# DATALOGGER_CA_ADC_V1.net
KiCad netlist of a schematic drawn in EAGLE
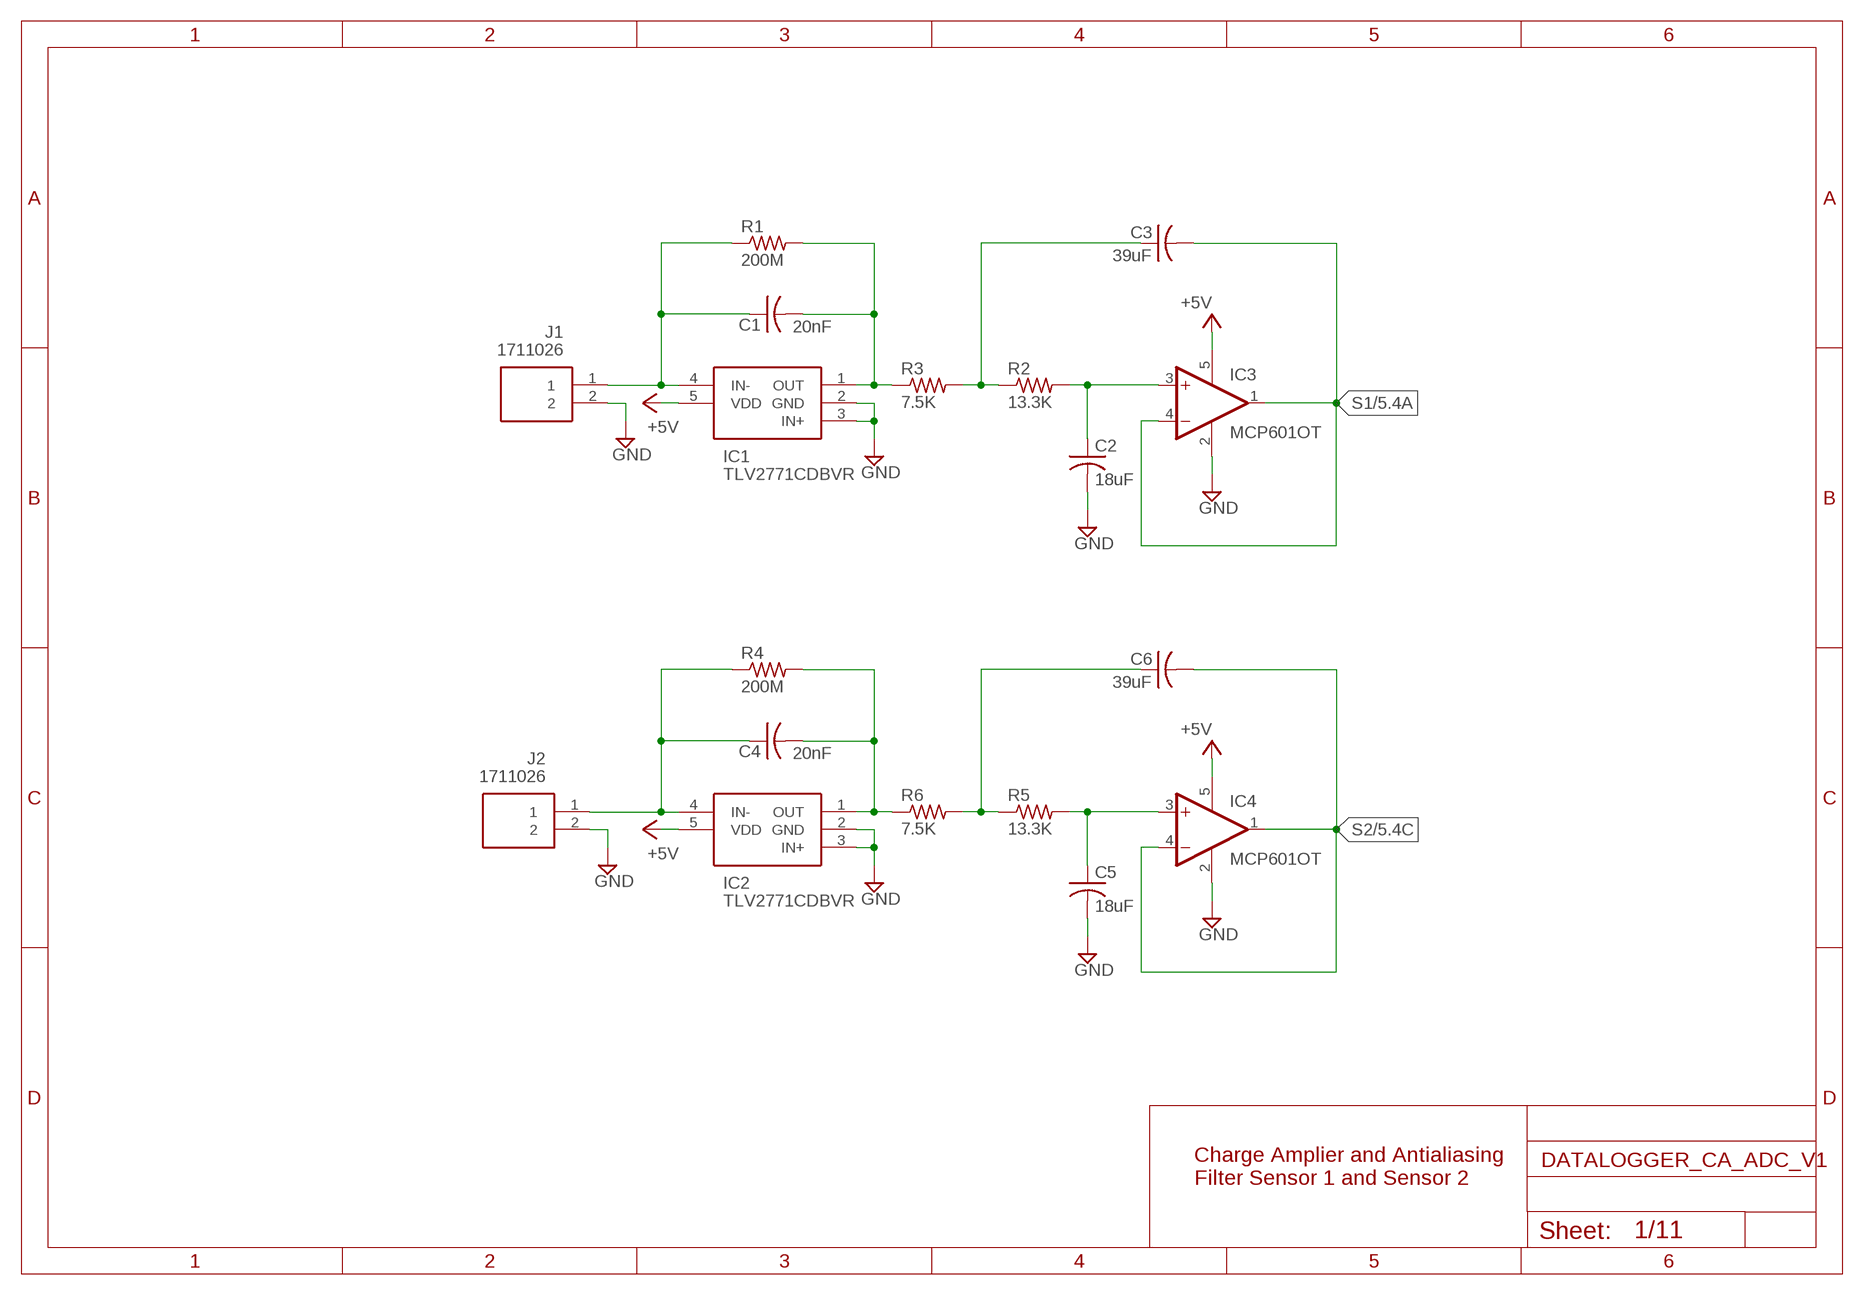
[diagram p0: schematic, sheet 1]
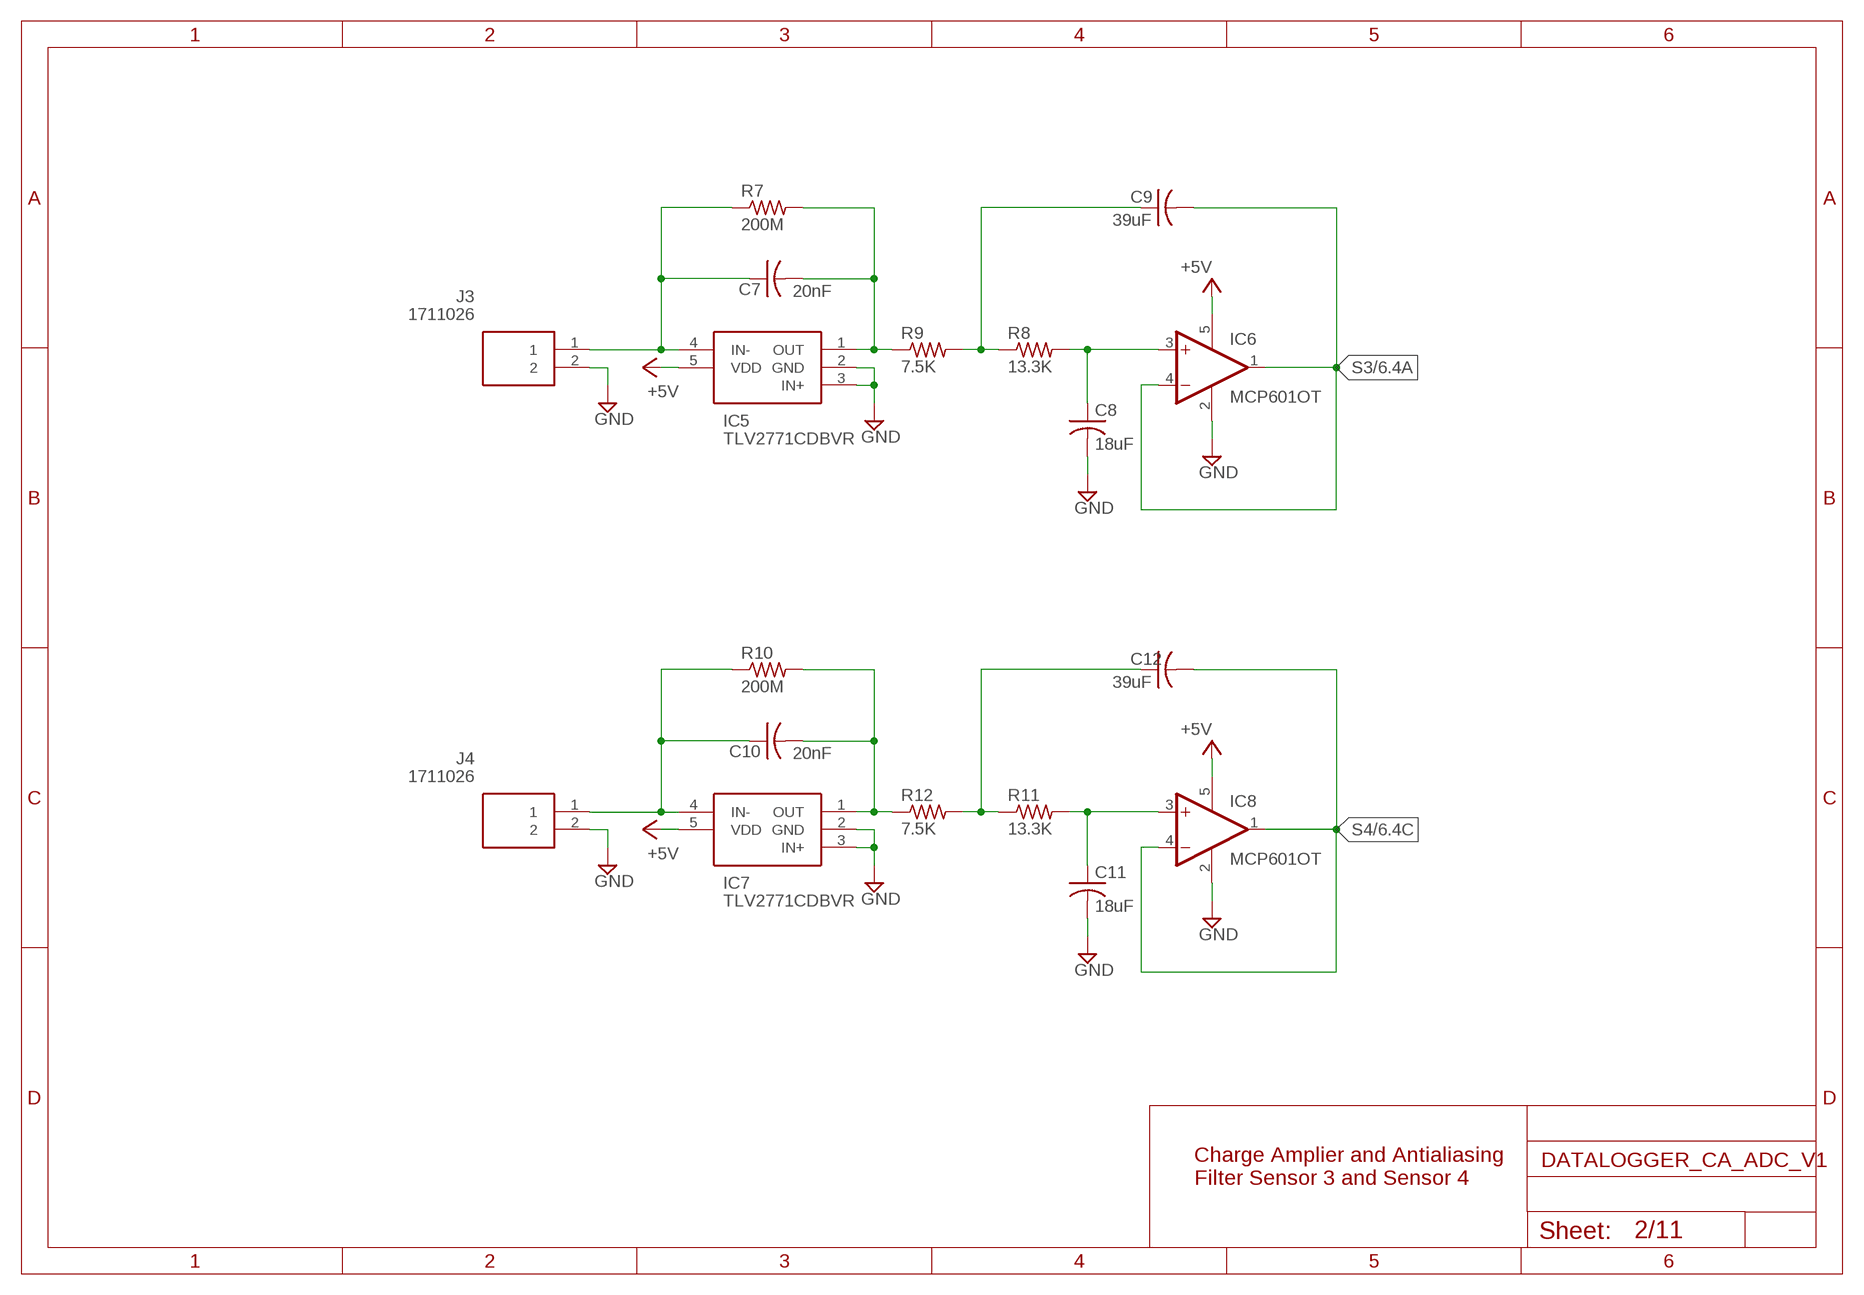
[diagram p1: schematic, sheet 2]
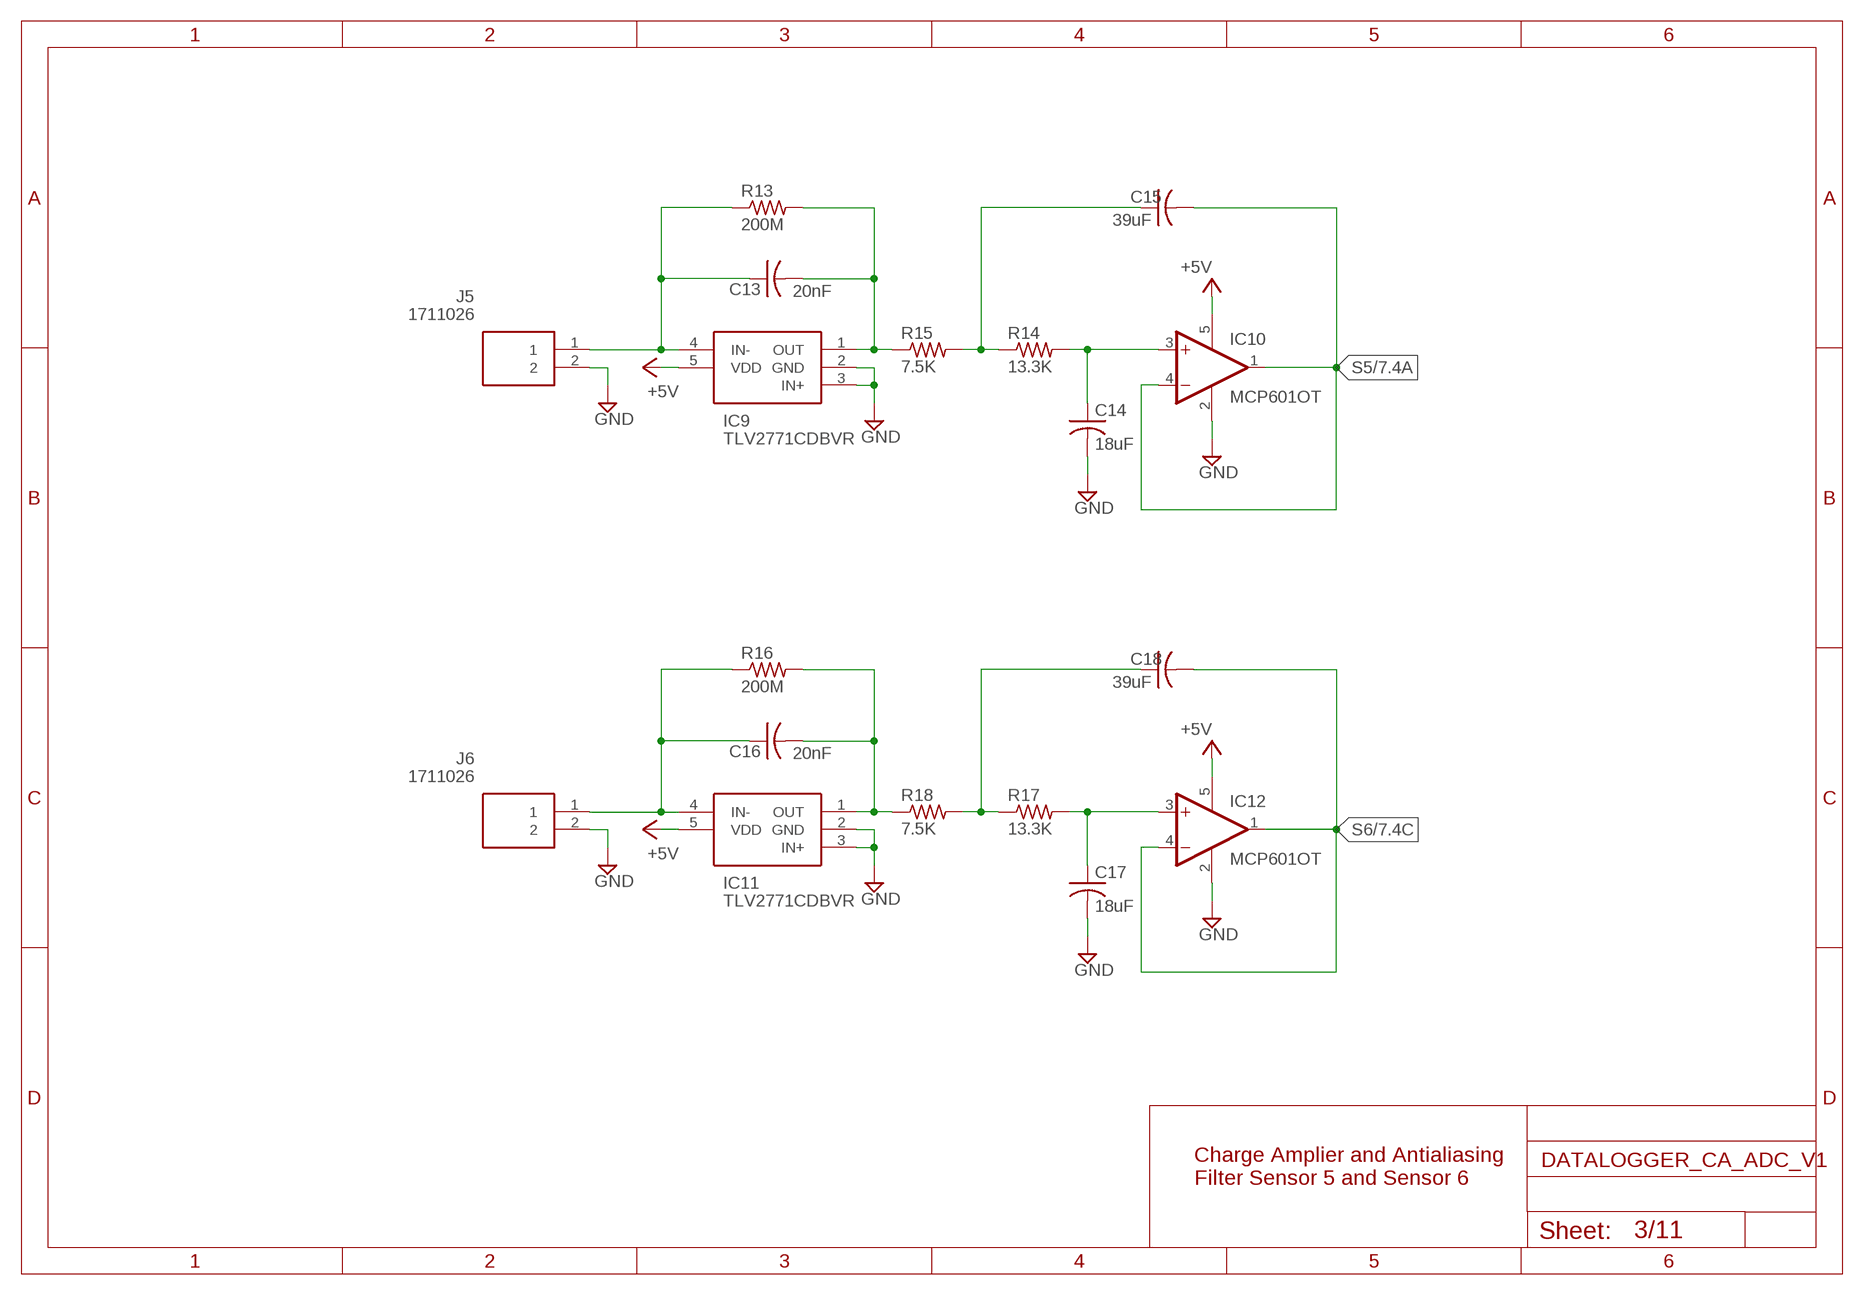
[diagram p2: schematic, sheet 3]
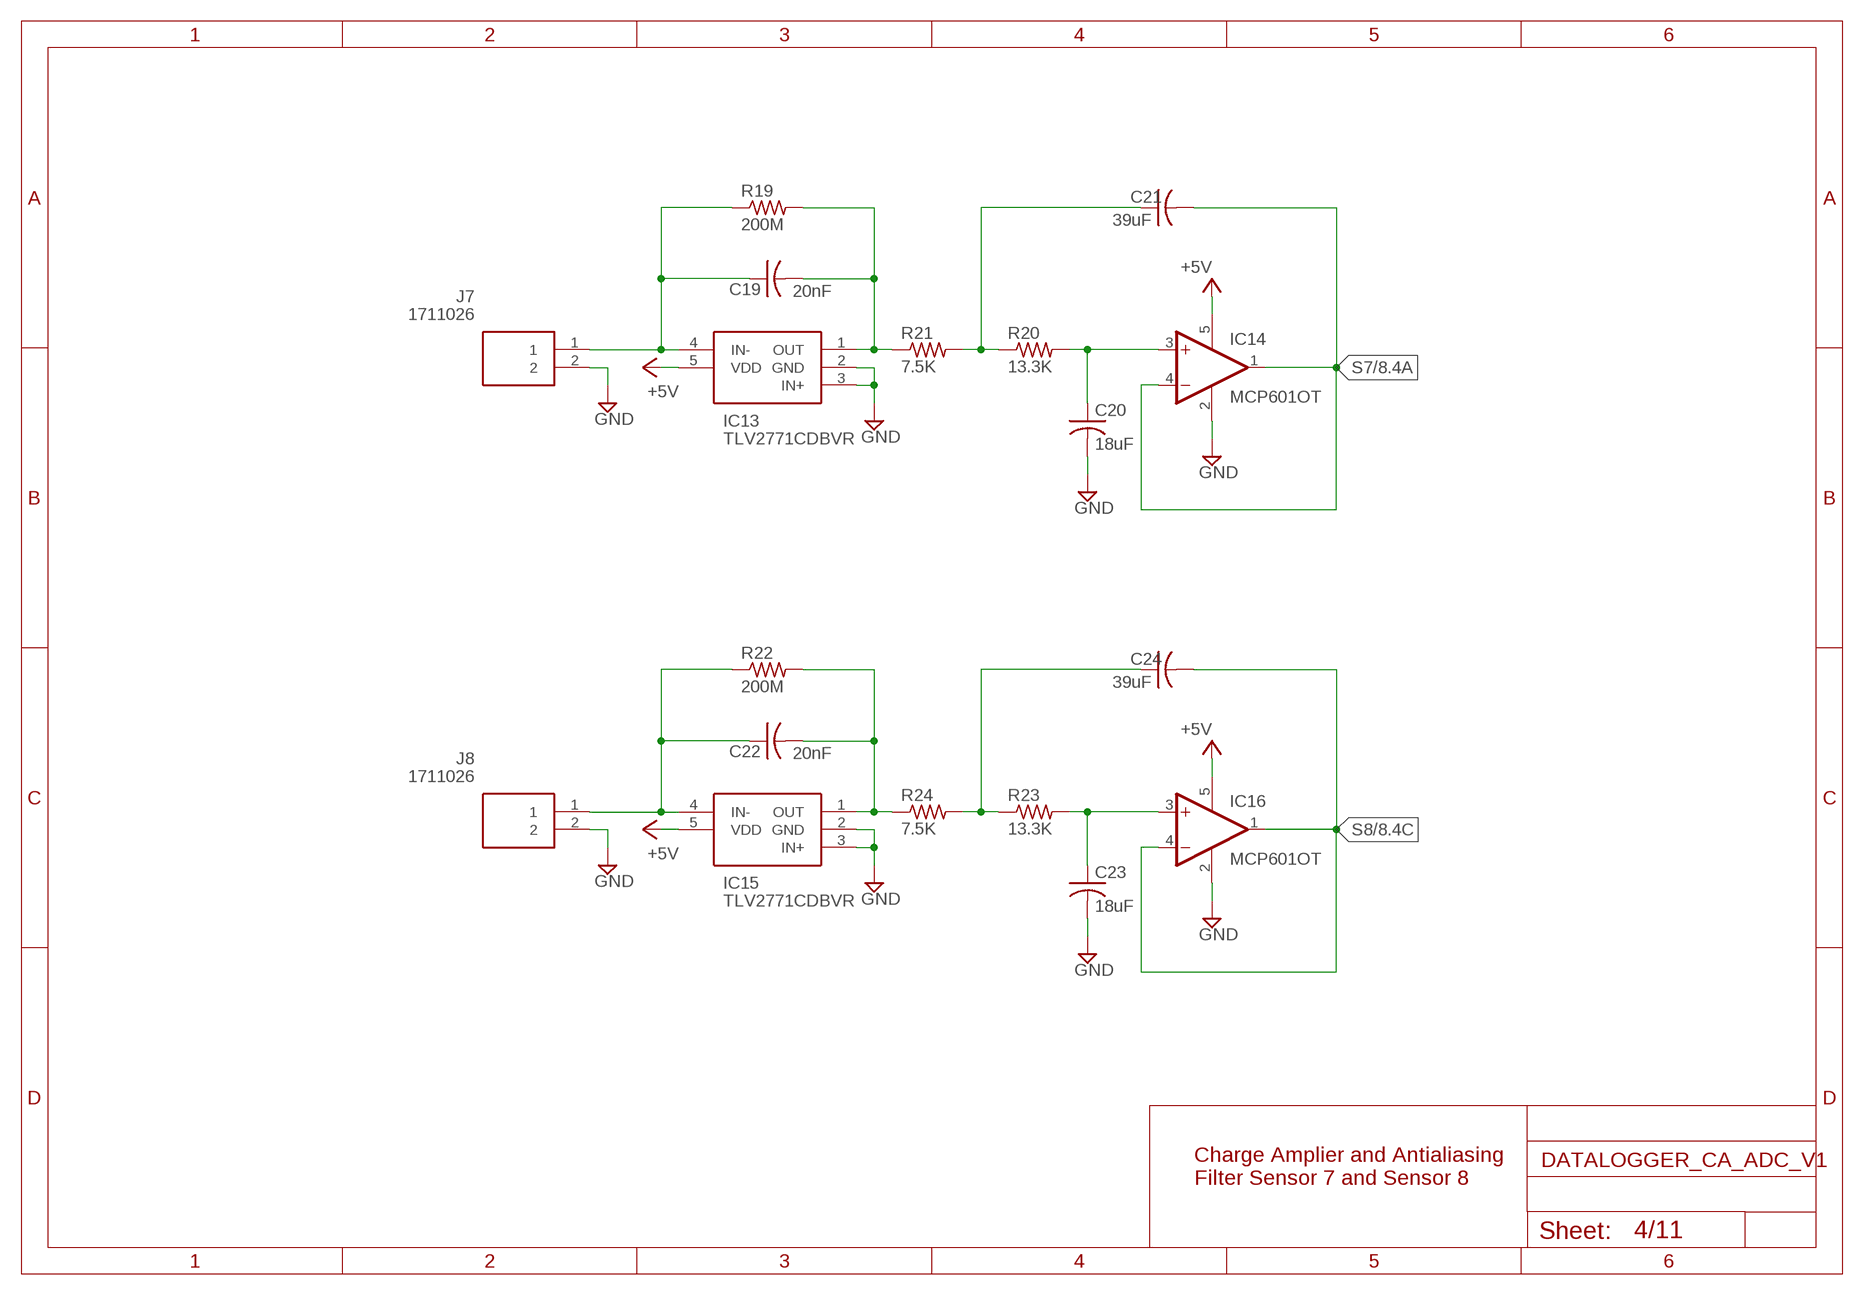
[diagram p3: schematic, sheet 4]
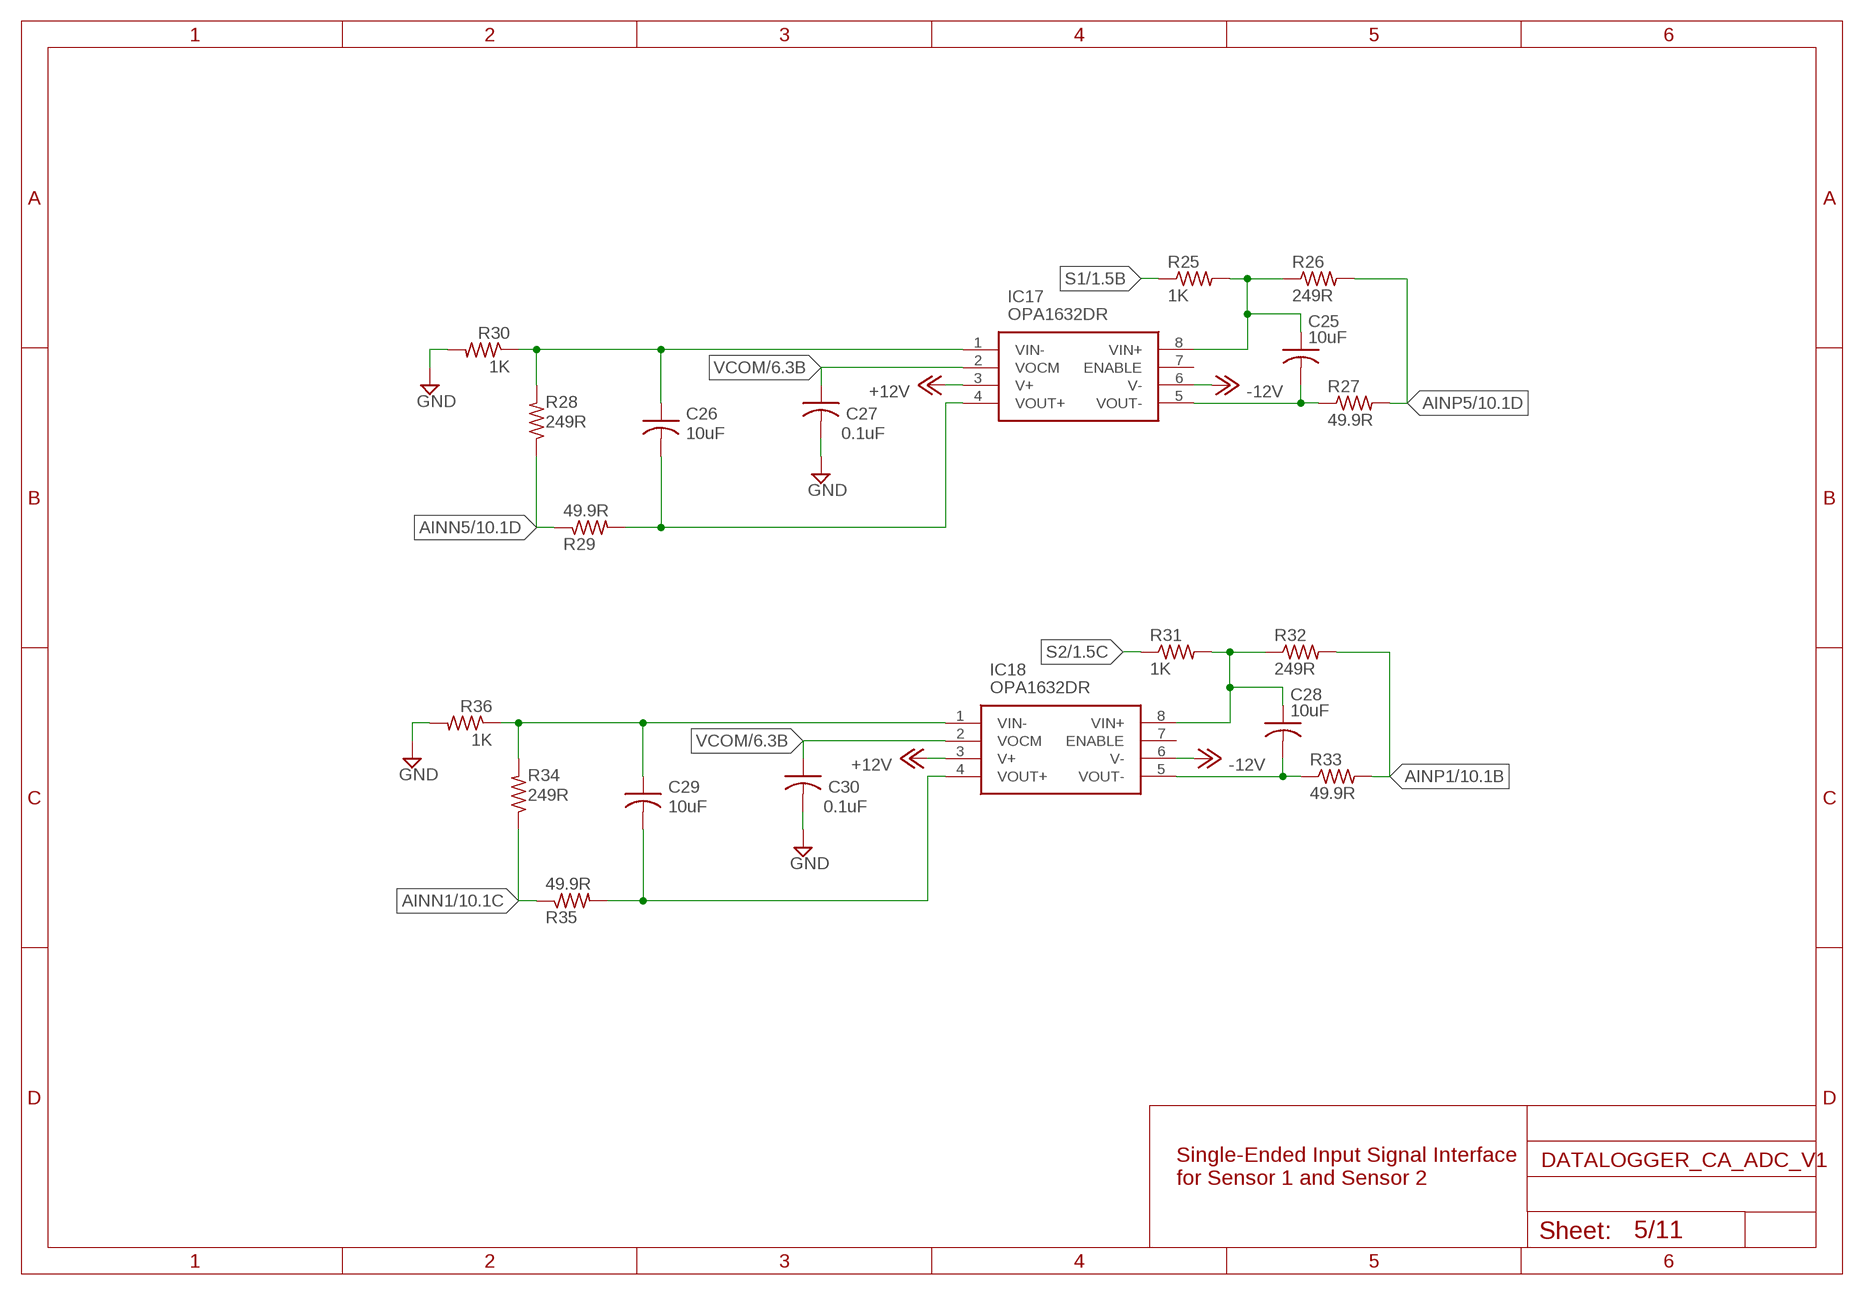
[diagram p4: schematic, sheet 5]
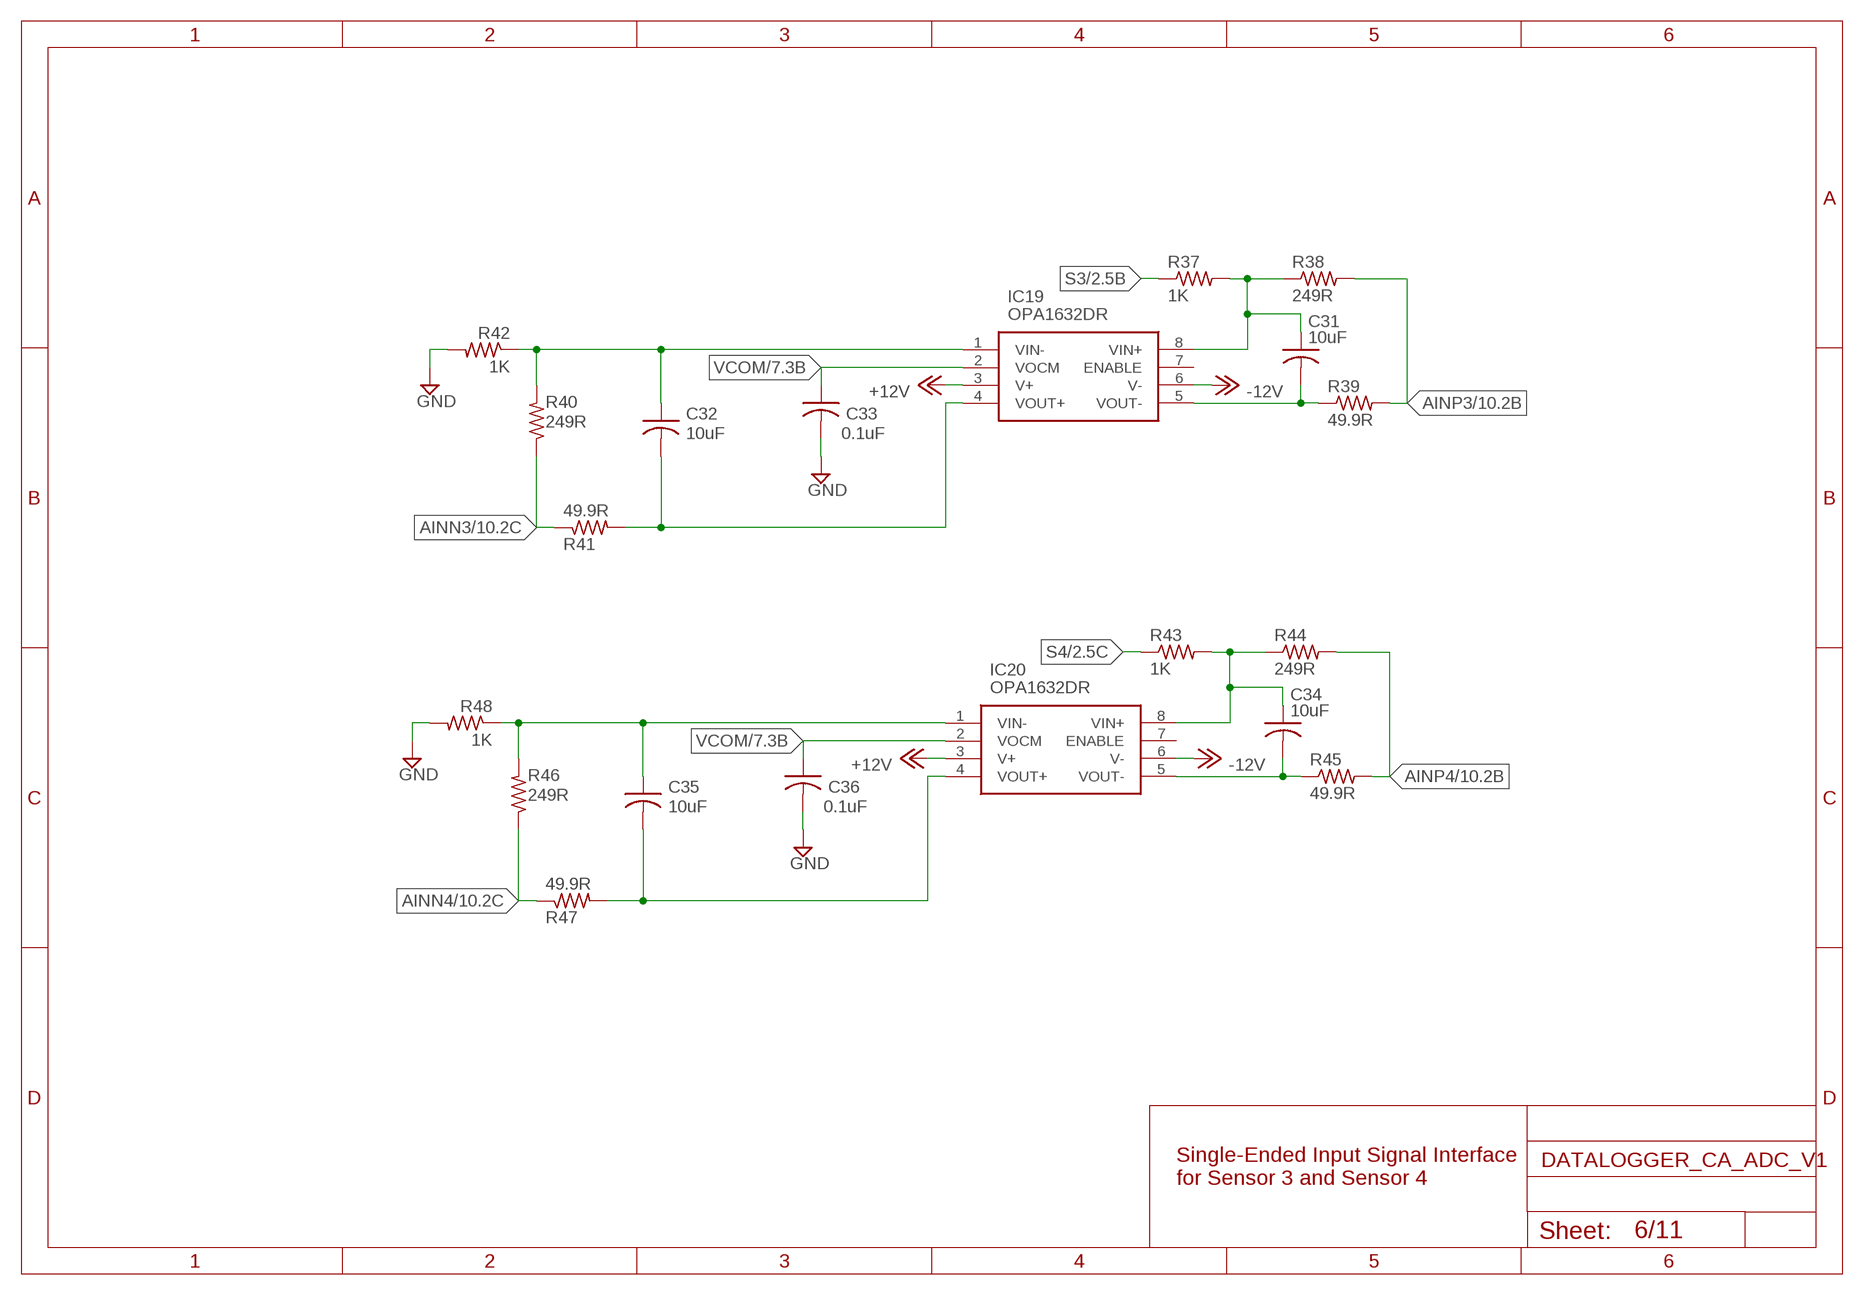
[diagram p5: schematic, sheet 6]
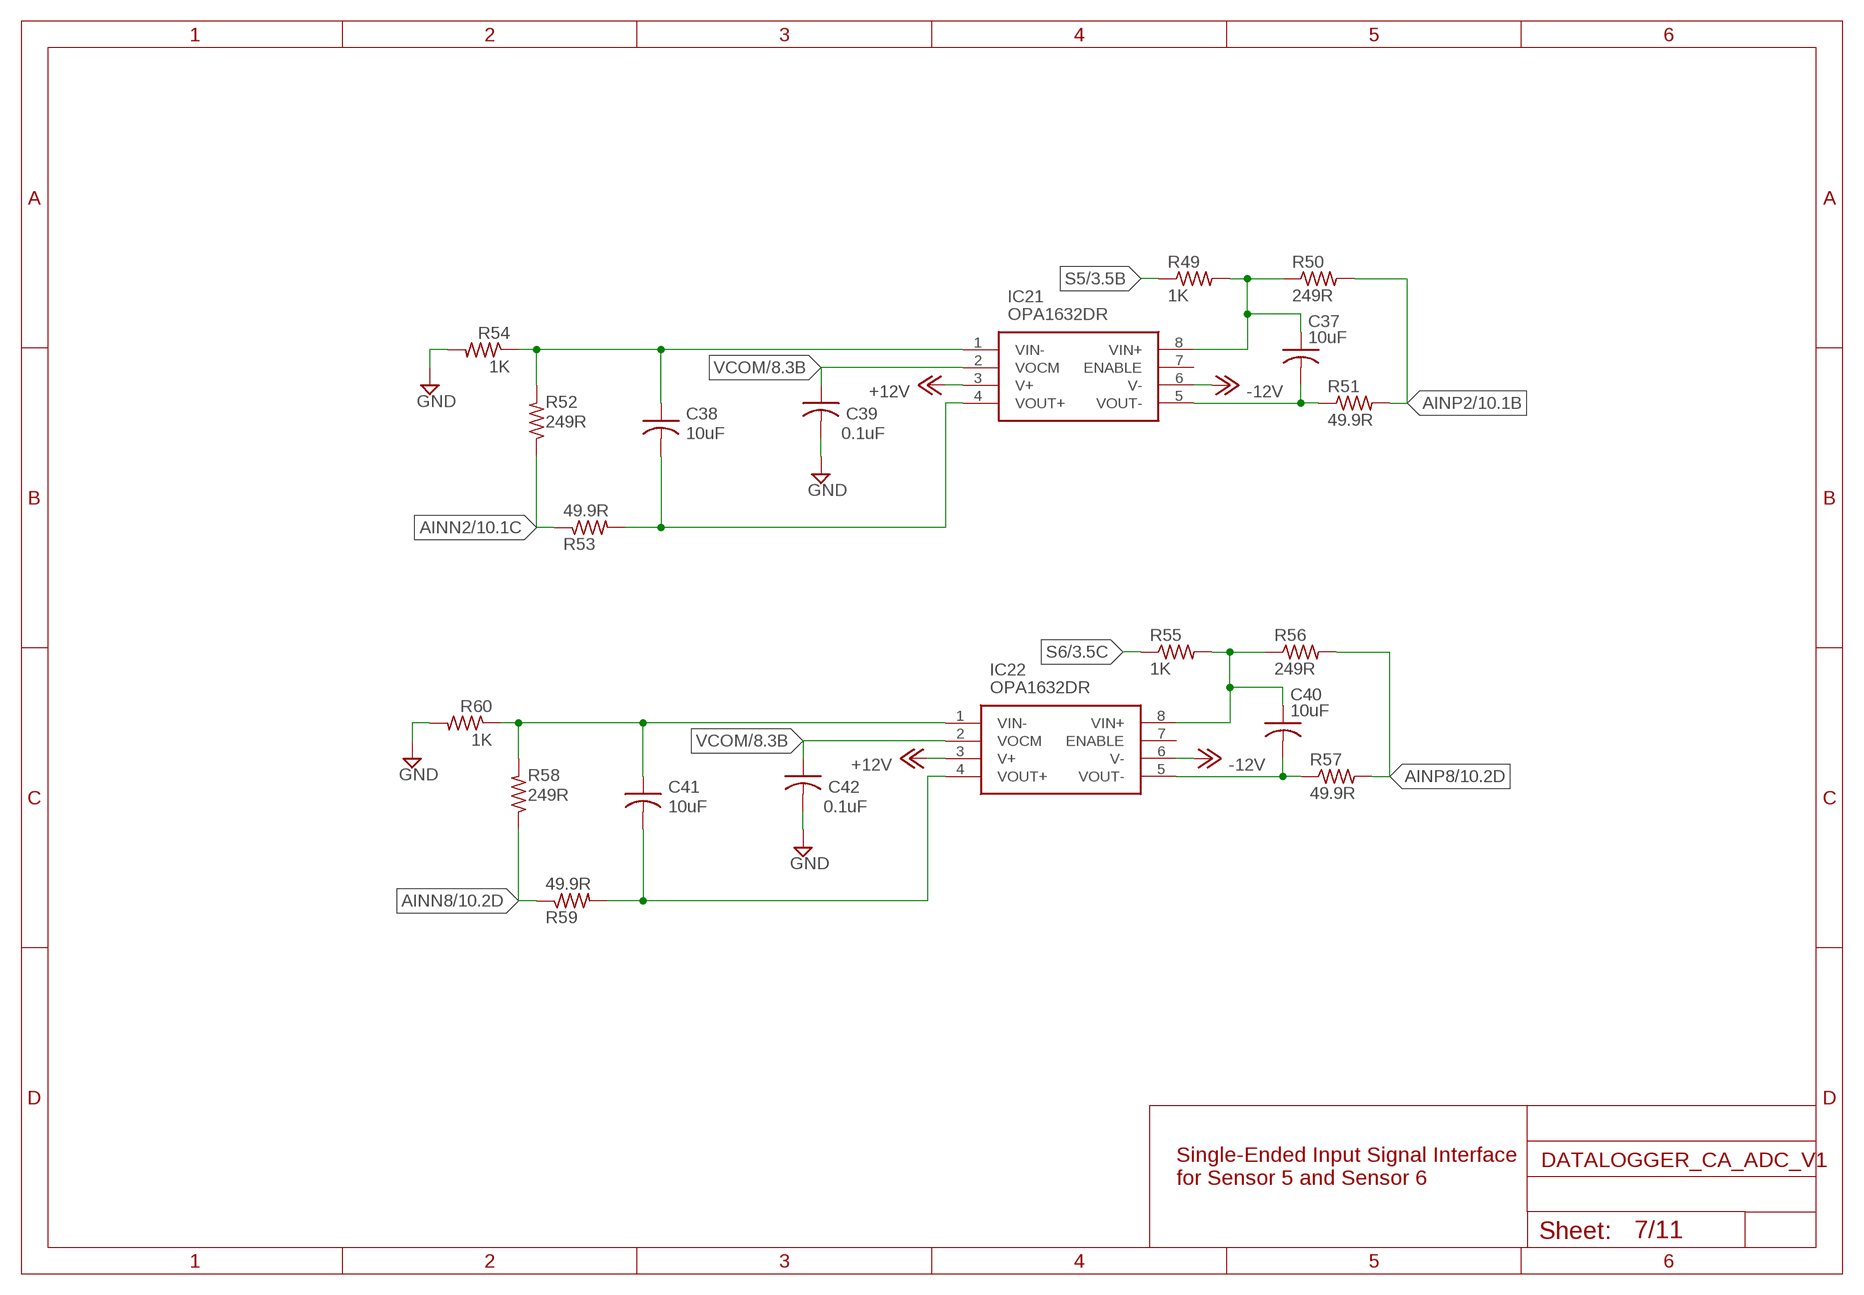
[diagram p6: schematic, sheet 7]
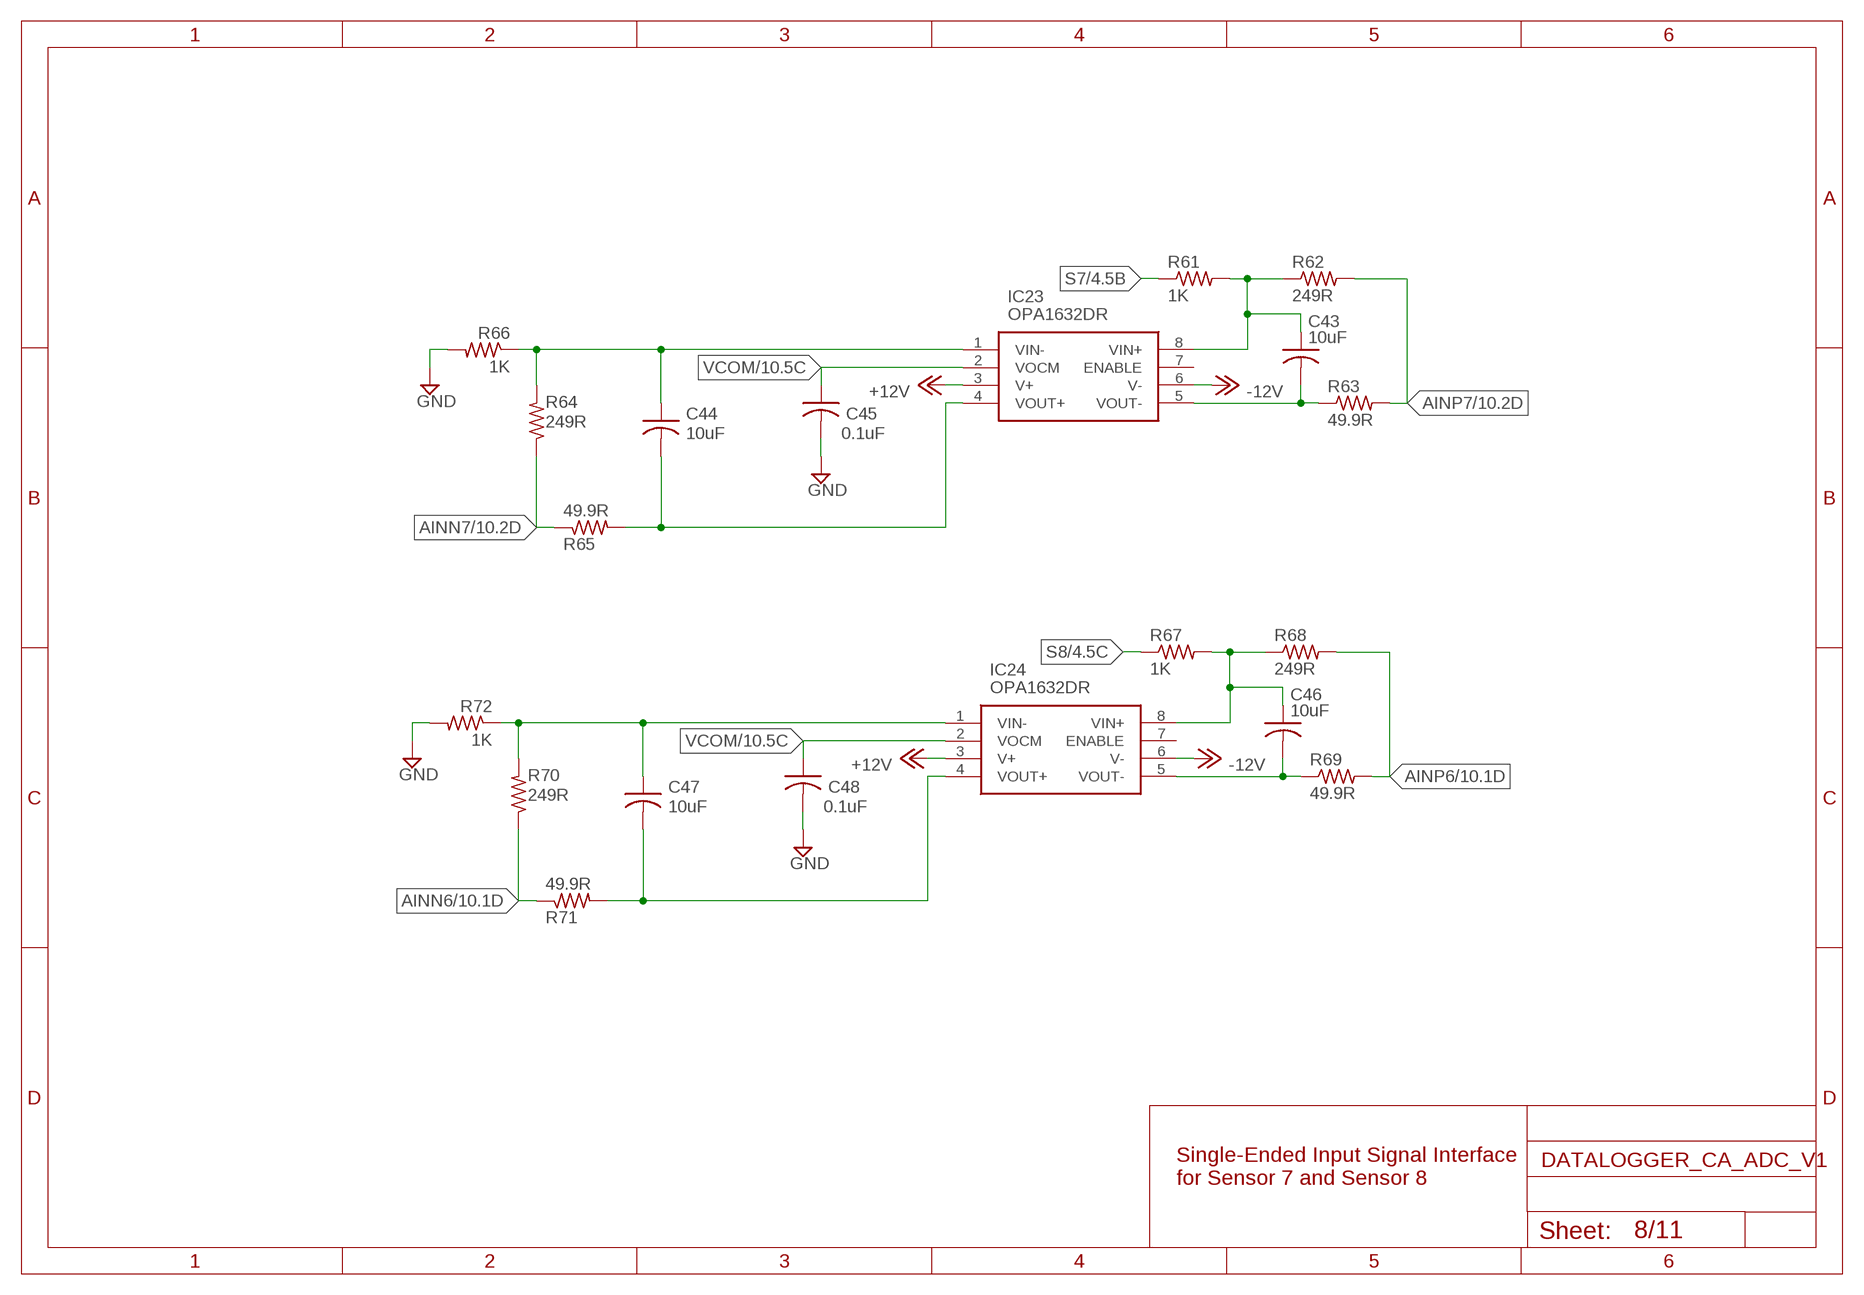
[diagram p7: schematic, sheet 8]
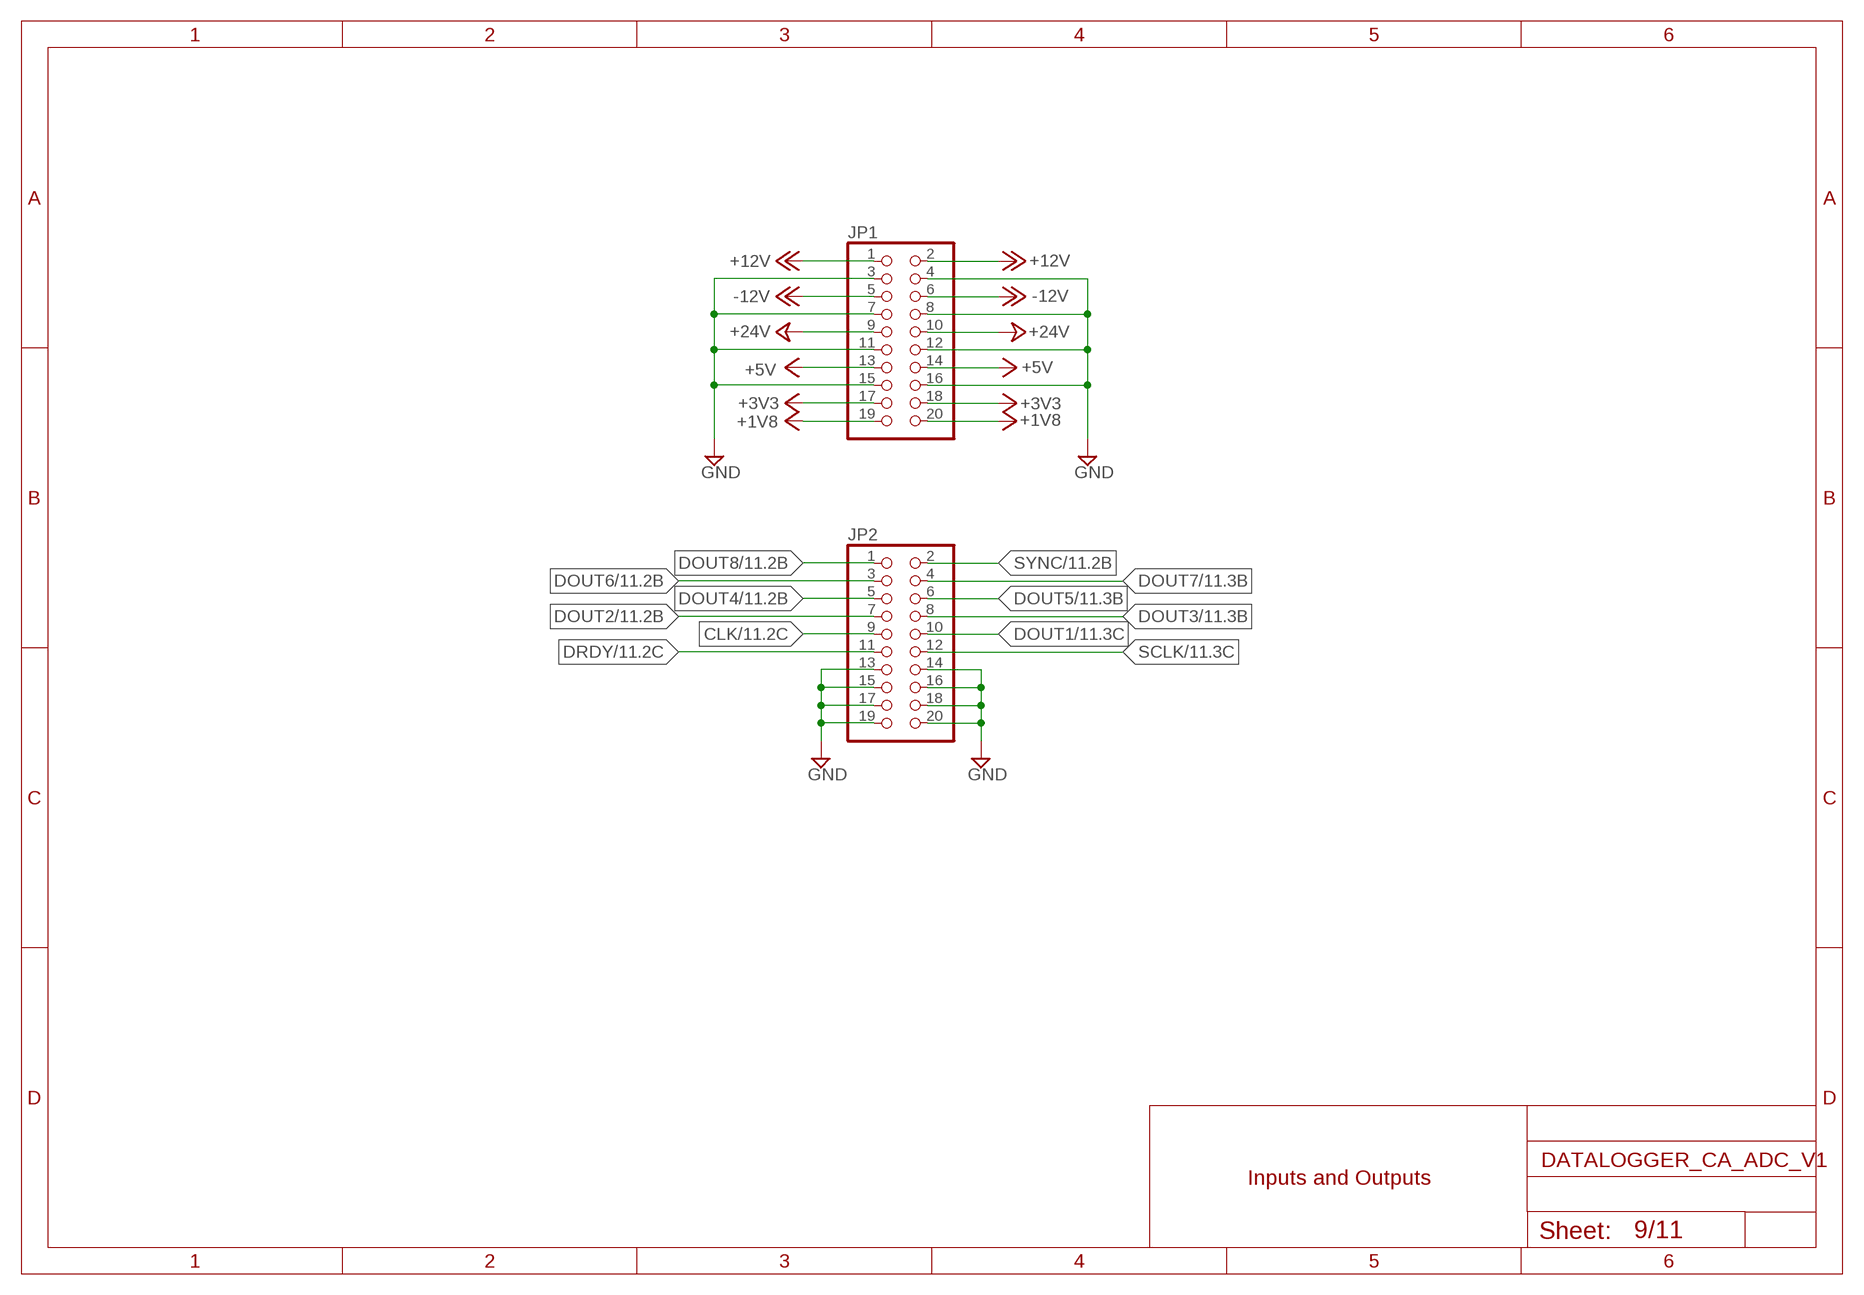
[diagram p8: schematic, sheet 9]
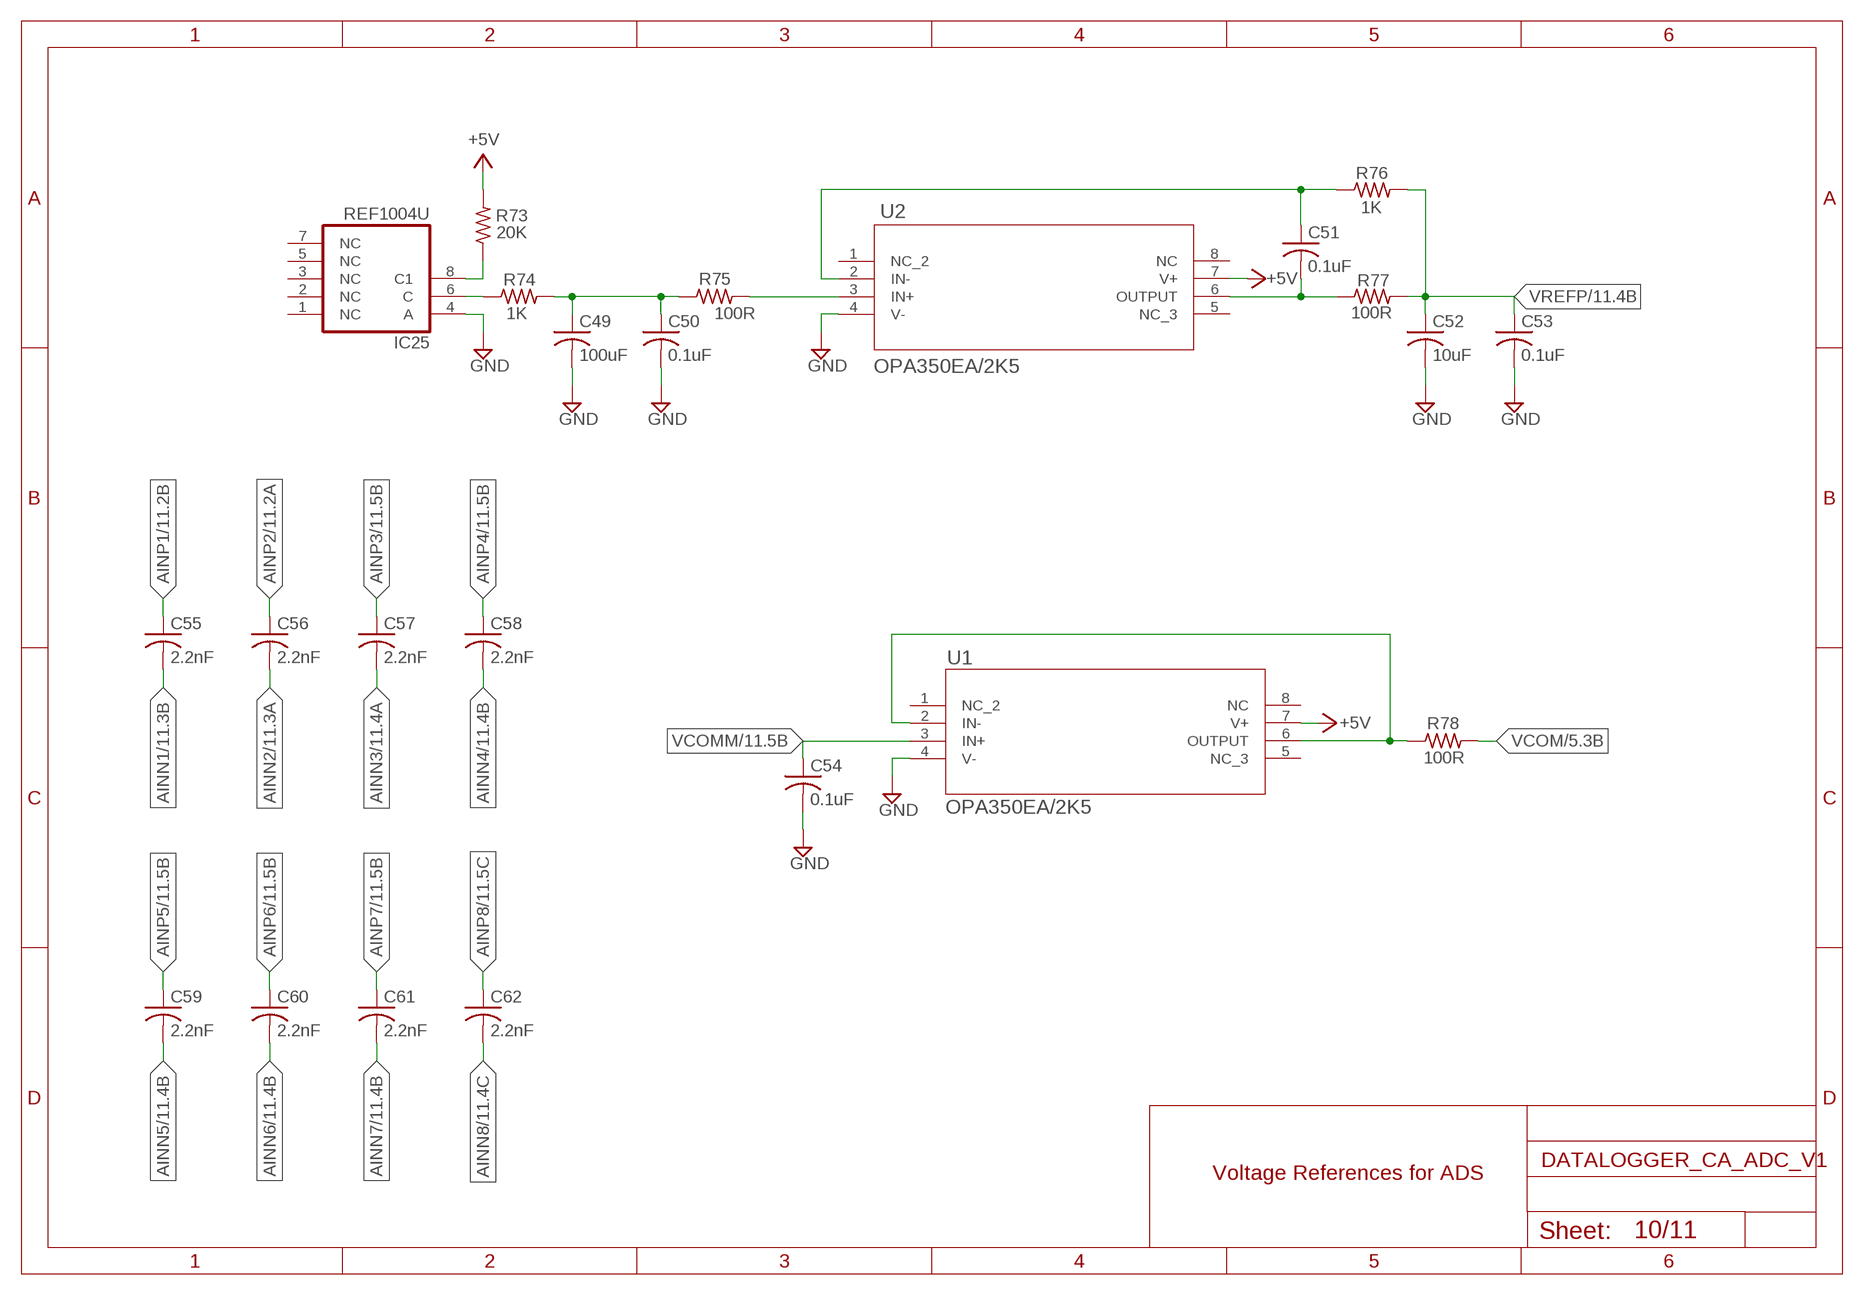
[diagram p9: schematic, sheet 10]
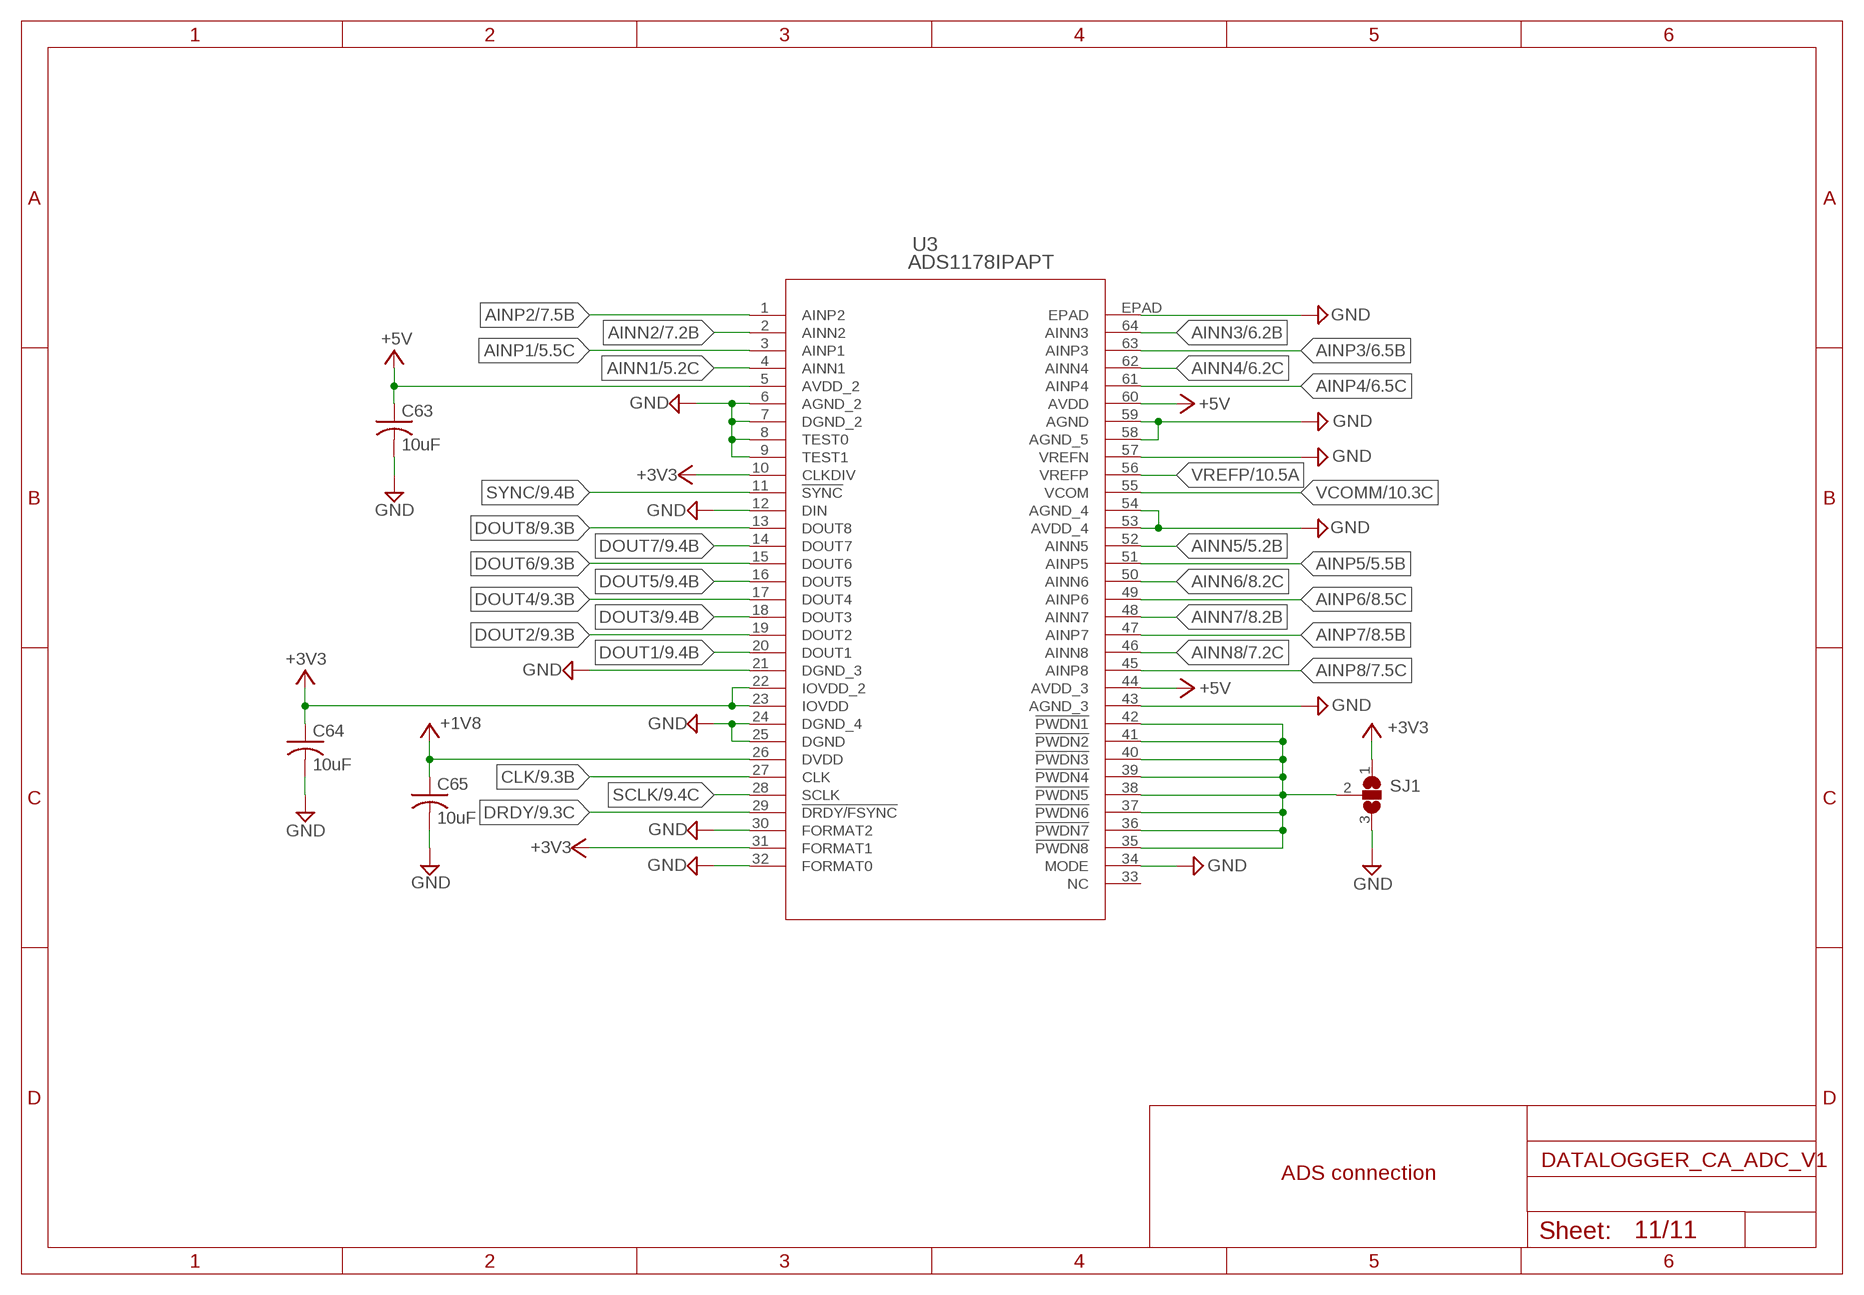
[diagram p10: schematic, sheet 11]

(export (version "E")
  (design (tool "Eeschema 10.0.6"))
  (components
    (comp (ref "JP1")
      (value "PINHD-2X10")
      (footprint "eagle-import:2X10")
      (libsource (lib "eagle-import") (part "PINHD-2X10"))
    )
    (comp (ref "JP2")
      (value "PINHD-2X10")
      (footprint "eagle-import:2X10")
      (libsource (lib "eagle-import") (part "PINHD-2X10"))
    )
    (comp (ref "C63")
      (value "10uF")
      (footprint "eagle-import:C0805")
      (libsource (lib "eagle-import") (part "C-USC0805"))
    )
    (comp (ref "C64")
      (value "10uF")
      (footprint "eagle-import:C0805")
      (libsource (lib "eagle-import") (part "C-USC0805"))
    )
    (comp (ref "C65")
      (value "10uF")
      (footprint "eagle-import:C0805")
      (libsource (lib "eagle-import") (part "C-USC0805"))
    )
    (comp (ref "SJ1")
      (value "SJ2W")
      (footprint "eagle-import:SJ_2")
      (libsource (lib "eagle-import") (part "SJ2W"))
    )
    (comp (ref "U3")
      (value "ADS1178IPAPT")
      (footprint "eagle-import:PAP64_TEX")
      (libsource (lib "eagle-import") (part "ADS1178IPAPT"))
    )
    (comp (ref "C19")
      (value "20nF")
      (footprint "eagle-import:C0805")
      (libsource (lib "eagle-import") (part "C-USC0805"))
    )
    (comp (ref "C20")
      (value "18uF")
      (footprint "eagle-import:C0805")
      (libsource (lib "eagle-import") (part "C-USC0805"))
    )
    (comp (ref "C21")
      (value "39uF")
      (footprint "eagle-import:C0805")
      (libsource (lib "eagle-import") (part "C-USC0805"))
    )
    (comp (ref "C22")
      (value "20nF")
      (footprint "eagle-import:C0805")
      (libsource (lib "eagle-import") (part "C-USC0805"))
    )
    (comp (ref "C23")
      (value "18uF")
      (footprint "eagle-import:C0805")
      (libsource (lib "eagle-import") (part "C-USC0805"))
    )
    (comp (ref "C24")
      (value "39uF")
      (footprint "eagle-import:C0805")
      (libsource (lib "eagle-import") (part "C-USC0805"))
    )
    (comp (ref "IC13")
      (value "TLV2771CDBVR")
      (footprint "eagle-import:SOT95P280X145-5N")
      (fields (field (name "MOUSER_PART_NUMBER") "595-TLV2771CDBVR"))
      (libsource (lib "eagle-import") (part "TLV2771CDBVR"))
    )
    (comp (ref "IC14")
      (value "MCP601OT")
      (footprint "eagle-import:SOT23-5")
      (libsource (lib "eagle-import") (part "MCP601OT"))
    )
    (comp (ref "IC15")
      (value "TLV2771CDBVR")
      (footprint "eagle-import:SOT95P280X145-5N")
      (fields (field (name "MOUSER_PART_NUMBER") "595-TLV2771CDBVR"))
      (libsource (lib "eagle-import") (part "TLV2771CDBVR"))
    )
    (comp (ref "IC16")
      (value "MCP601OT")
      (footprint "eagle-import:SOT23-5")
      (libsource (lib "eagle-import") (part "MCP601OT"))
    )
    (comp (ref "J7")
      (value "1711026")
      (footprint "eagle-import:SHDR2W110P0X500_1X2_1000X1120X")
      (fields (field (name "MOUSER_PART_NUMBER") "651-1711026"))
      (libsource (lib "eagle-import") (part "1711026"))
    )
    (comp (ref "J8")
      (value "1711026")
      (footprint "eagle-import:SHDR2W110P0X500_1X2_1000X1120X")
      (fields (field (name "MOUSER_PART_NUMBER") "651-1711026"))
      (libsource (lib "eagle-import") (part "1711026"))
    )
    (comp (ref "R19")
      (value "200M")
      (footprint "eagle-import:R0805")
      (libsource (lib "eagle-import") (part "R-US_R0805"))
    )
    (comp (ref "R20")
      (value "13.3K")
      (footprint "eagle-import:R0805")
      (libsource (lib "eagle-import") (part "R-US_R0805"))
    )
    (comp (ref "R21")
      (value "7.5K")
      (footprint "eagle-import:R0805")
      (libsource (lib "eagle-import") (part "R-US_R0805"))
    )
    (comp (ref "R22")
      (value "200M")
      (footprint "eagle-import:R0805")
      (libsource (lib "eagle-import") (part "R-US_R0805"))
    )
    (comp (ref "R23")
      (value "13.3K")
      (footprint "eagle-import:R0805")
      (libsource (lib "eagle-import") (part "R-US_R0805"))
    )
    (comp (ref "R24")
      (value "7.5K")
      (footprint "eagle-import:R0805")
      (libsource (lib "eagle-import") (part "R-US_R0805"))
    )
    (comp (ref "C13")
      (value "20nF")
      (footprint "eagle-import:C0805")
      (libsource (lib "eagle-import") (part "C-USC0805"))
    )
    (comp (ref "C14")
      (value "18uF")
      (footprint "eagle-import:C0805")
      (libsource (lib "eagle-import") (part "C-USC0805"))
    )
    (comp (ref "C15")
      (value "39uF")
      (footprint "eagle-import:C0805")
      (libsource (lib "eagle-import") (part "C-USC0805"))
    )
    (comp (ref "C16")
      (value "20nF")
      (footprint "eagle-import:C0805")
      (libsource (lib "eagle-import") (part "C-USC0805"))
    )
    (comp (ref "C17")
      (value "18uF")
      (footprint "eagle-import:C0805")
      (libsource (lib "eagle-import") (part "C-USC0805"))
    )
    (comp (ref "C18")
      (value "39uF")
      (footprint "eagle-import:C0805")
      (libsource (lib "eagle-import") (part "C-USC0805"))
    )
    (comp (ref "IC9")
      (value "TLV2771CDBVR")
      (footprint "eagle-import:SOT95P280X145-5N")
      (fields (field (name "MOUSER_PART_NUMBER") "595-TLV2771CDBVR"))
      (libsource (lib "eagle-import") (part "TLV2771CDBVR"))
    )
    (comp (ref "IC10")
      (value "MCP601OT")
      (footprint "eagle-import:SOT23-5")
      (libsource (lib "eagle-import") (part "MCP601OT"))
    )
    (comp (ref "IC11")
      (value "TLV2771CDBVR")
      (footprint "eagle-import:SOT95P280X145-5N")
      (fields (field (name "MOUSER_PART_NUMBER") "595-TLV2771CDBVR"))
      (libsource (lib "eagle-import") (part "TLV2771CDBVR"))
    )
    (comp (ref "IC12")
      (value "MCP601OT")
      (footprint "eagle-import:SOT23-5")
      (libsource (lib "eagle-import") (part "MCP601OT"))
    )
    (comp (ref "J5")
      (value "1711026")
      (footprint "eagle-import:SHDR2W110P0X500_1X2_1000X1120X")
      (fields (field (name "MOUSER_PART_NUMBER") "651-1711026"))
      (libsource (lib "eagle-import") (part "1711026"))
    )
    (comp (ref "J6")
      (value "1711026")
      (footprint "eagle-import:SHDR2W110P0X500_1X2_1000X1120X")
      (fields (field (name "MOUSER_PART_NUMBER") "651-1711026"))
      (libsource (lib "eagle-import") (part "1711026"))
    )
    (comp (ref "R13")
      (value "200M")
      (footprint "eagle-import:R0805")
      (libsource (lib "eagle-import") (part "R-US_R0805"))
    )
    (comp (ref "R14")
      (value "13.3K")
      (footprint "eagle-import:R0805")
      (libsource (lib "eagle-import") (part "R-US_R0805"))
    )
    (comp (ref "R15")
      (value "7.5K")
      (footprint "eagle-import:R0805")
      (libsource (lib "eagle-import") (part "R-US_R0805"))
    )
    (comp (ref "R16")
      (value "200M")
      (footprint "eagle-import:R0805")
      (libsource (lib "eagle-import") (part "R-US_R0805"))
    )
    (comp (ref "R17")
      (value "13.3K")
      (footprint "eagle-import:R0805")
      (libsource (lib "eagle-import") (part "R-US_R0805"))
    )
    (comp (ref "R18")
      (value "7.5K")
      (footprint "eagle-import:R0805")
      (libsource (lib "eagle-import") (part "R-US_R0805"))
    )
    (comp (ref "C43")
      (value "10uF")
      (footprint "eagle-import:C0805")
      (libsource (lib "eagle-import") (part "C-USC0805"))
    )
    (comp (ref "C44")
      (value "10uF")
      (footprint "eagle-import:C0805")
      (libsource (lib "eagle-import") (part "C-USC0805"))
    )
    (comp (ref "C45")
      (value "0.1uF")
      (footprint "eagle-import:C0805")
      (libsource (lib "eagle-import") (part "C-USC0805"))
    )
    (comp (ref "C46")
      (value "10uF")
      (footprint "eagle-import:C0805")
      (libsource (lib "eagle-import") (part "C-USC0805"))
    )
    (comp (ref "C47")
      (value "10uF")
      (footprint "eagle-import:C0805")
      (libsource (lib "eagle-import") (part "C-USC0805"))
    )
    (comp (ref "C48")
      (value "0.1uF")
      (footprint "eagle-import:C0805")
      (libsource (lib "eagle-import") (part "C-USC0805"))
    )
    (comp (ref "IC23")
      (value "OPA1632DR")
      (footprint "eagle-import:SOIC127P600X175-8N")
      (fields (field (name "MOUSER_PART_NUMBER") "595-OPA1632DR"))
      (libsource (lib "eagle-import") (part "OPA1632DR"))
    )
    (comp (ref "IC24")
      (value "OPA1632DR")
      (footprint "eagle-import:SOIC127P600X175-8N")
      (fields (field (name "MOUSER_PART_NUMBER") "595-OPA1632DR"))
      (libsource (lib "eagle-import") (part "OPA1632DR"))
    )
    (comp (ref "R61")
      (value "1K")
      (footprint "eagle-import:R0805")
      (libsource (lib "eagle-import") (part "R-US_R0805"))
    )
    (comp (ref "R62")
      (value "249R")
      (footprint "eagle-import:R0805")
      (libsource (lib "eagle-import") (part "R-US_R0805"))
    )
    (comp (ref "R63")
      (value "49.9R")
      (footprint "eagle-import:R0805")
      (libsource (lib "eagle-import") (part "R-US_R0805"))
    )
    (comp (ref "R64")
      (value "249R")
      (footprint "eagle-import:R0805")
      (libsource (lib "eagle-import") (part "R-US_R0805"))
    )
    (comp (ref "R65")
      (value "49.9R")
      (footprint "eagle-import:R0805")
      (libsource (lib "eagle-import") (part "R-US_R0805"))
    )
    (comp (ref "R66")
      (value "1K")
      (footprint "eagle-import:R0805")
      (libsource (lib "eagle-import") (part "R-US_R0805"))
    )
    (comp (ref "R67")
      (value "1K")
      (footprint "eagle-import:R0805")
      (libsource (lib "eagle-import") (part "R-US_R0805"))
    )
    (comp (ref "R68")
      (value "249R")
      (footprint "eagle-import:R0805")
      (libsource (lib "eagle-import") (part "R-US_R0805"))
    )
    (comp (ref "R69")
      (value "49.9R")
      (footprint "eagle-import:R0805")
      (libsource (lib "eagle-import") (part "R-US_R0805"))
    )
    (comp (ref "R70")
      (value "249R")
      (footprint "eagle-import:R0805")
      (libsource (lib "eagle-import") (part "R-US_R0805"))
    )
    (comp (ref "R71")
      (value "49.9R")
      (footprint "eagle-import:R0805")
      (libsource (lib "eagle-import") (part "R-US_R0805"))
    )
    (comp (ref "R72")
      (value "1K")
      (footprint "eagle-import:R0805")
      (libsource (lib "eagle-import") (part "R-US_R0805"))
    )
    (comp (ref "C31")
      (value "10uF")
      (footprint "eagle-import:C0805")
      (libsource (lib "eagle-import") (part "C-USC0805"))
    )
    (comp (ref "C32")
      (value "10uF")
      (footprint "eagle-import:C0805")
      (libsource (lib "eagle-import") (part "C-USC0805"))
    )
    (comp (ref "C33")
      (value "0.1uF")
      (footprint "eagle-import:C0805")
      (libsource (lib "eagle-import") (part "C-USC0805"))
    )
    (comp (ref "C34")
      (value "10uF")
      (footprint "eagle-import:C0805")
      (libsource (lib "eagle-import") (part "C-USC0805"))
    )
    (comp (ref "C35")
      (value "10uF")
      (footprint "eagle-import:C0805")
      (libsource (lib "eagle-import") (part "C-USC0805"))
    )
    (comp (ref "C36")
      (value "0.1uF")
      (footprint "eagle-import:C0805")
      (libsource (lib "eagle-import") (part "C-USC0805"))
    )
    (comp (ref "IC19")
      (value "OPA1632DR")
      (footprint "eagle-import:SOIC127P600X175-8N")
      (fields (field (name "MOUSER_PART_NUMBER") "595-OPA1632DR"))
      (libsource (lib "eagle-import") (part "OPA1632DR"))
    )
    (comp (ref "IC20")
      (value "OPA1632DR")
      (footprint "eagle-import:SOIC127P600X175-8N")
      (fields (field (name "MOUSER_PART_NUMBER") "595-OPA1632DR"))
      (libsource (lib "eagle-import") (part "OPA1632DR"))
    )
    (comp (ref "R37")
      (value "1K")
      (footprint "eagle-import:R0805")
      (libsource (lib "eagle-import") (part "R-US_R0805"))
    )
    (comp (ref "R38")
      (value "249R")
      (footprint "eagle-import:R0805")
      (libsource (lib "eagle-import") (part "R-US_R0805"))
    )
    (comp (ref "R39")
      (value "49.9R")
      (footprint "eagle-import:R0805")
      (libsource (lib "eagle-import") (part "R-US_R0805"))
    )
    (comp (ref "R40")
      (value "249R")
      (footprint "eagle-import:R0805")
      (libsource (lib "eagle-import") (part "R-US_R0805"))
    )
    (comp (ref "R41")
      (value "49.9R")
      (footprint "eagle-import:R0805")
      (libsource (lib "eagle-import") (part "R-US_R0805"))
    )
    (comp (ref "R42")
      (value "1K")
      (footprint "eagle-import:R0805")
      (libsource (lib "eagle-import") (part "R-US_R0805"))
    )
    (comp (ref "R43")
      (value "1K")
      (footprint "eagle-import:R0805")
      (libsource (lib "eagle-import") (part "R-US_R0805"))
    )
    (comp (ref "R44")
      (value "249R")
      (footprint "eagle-import:R0805")
      (libsource (lib "eagle-import") (part "R-US_R0805"))
    )
    (comp (ref "R45")
      (value "49.9R")
      (footprint "eagle-import:R0805")
      (libsource (lib "eagle-import") (part "R-US_R0805"))
    )
    (comp (ref "R46")
      (value "249R")
      (footprint "eagle-import:R0805")
      (libsource (lib "eagle-import") (part "R-US_R0805"))
    )
    (comp (ref "R47")
      (value "49.9R")
      (footprint "eagle-import:R0805")
      (libsource (lib "eagle-import") (part "R-US_R0805"))
    )
    (comp (ref "R48")
      (value "1K")
      (footprint "eagle-import:R0805")
      (libsource (lib "eagle-import") (part "R-US_R0805"))
    )
    (comp (ref "C7")
      (value "20nF")
      (footprint "eagle-import:C0805")
      (libsource (lib "eagle-import") (part "C-USC0805"))
    )
    (comp (ref "C8")
      (value "18uF")
      (footprint "eagle-import:C0805")
      (libsource (lib "eagle-import") (part "C-USC0805"))
    )
    (comp (ref "C9")
      (value "39uF")
      (footprint "eagle-import:C0805")
      (libsource (lib "eagle-import") (part "C-USC0805"))
    )
    (comp (ref "C10")
      (value "20nF")
      (footprint "eagle-import:C0805")
      (libsource (lib "eagle-import") (part "C-USC0805"))
    )
    (comp (ref "C11")
      (value "18uF")
      (footprint "eagle-import:C0805")
      (libsource (lib "eagle-import") (part "C-USC0805"))
    )
    (comp (ref "C12")
      (value "39uF")
      (footprint "eagle-import:C0805")
      (libsource (lib "eagle-import") (part "C-USC0805"))
    )
    (comp (ref "IC5")
      (value "TLV2771CDBVR")
      (footprint "eagle-import:SOT95P280X145-5N")
      (fields (field (name "MOUSER_PART_NUMBER") "595-TLV2771CDBVR"))
      (libsource (lib "eagle-import") (part "TLV2771CDBVR"))
    )
    (comp (ref "IC6")
      (value "MCP601OT")
      (footprint "eagle-import:SOT23-5")
      (libsource (lib "eagle-import") (part "MCP601OT"))
    )
    (comp (ref "IC7")
      (value "TLV2771CDBVR")
      (footprint "eagle-import:SOT95P280X145-5N")
      (fields (field (name "MOUSER_PART_NUMBER") "595-TLV2771CDBVR"))
      (libsource (lib "eagle-import") (part "TLV2771CDBVR"))
    )
    (comp (ref "IC8")
      (value "MCP601OT")
      (footprint "eagle-import:SOT23-5")
      (libsource (lib "eagle-import") (part "MCP601OT"))
    )
    (comp (ref "J3")
      (value "1711026")
      (footprint "eagle-import:SHDR2W110P0X500_1X2_1000X1120X")
      (fields (field (name "MOUSER_PART_NUMBER") "651-1711026"))
      (libsource (lib "eagle-import") (part "1711026"))
    )
    (comp (ref "J4")
      (value "1711026")
      (footprint "eagle-import:SHDR2W110P0X500_1X2_1000X1120X")
      (fields (field (name "MOUSER_PART_NUMBER") "651-1711026"))
      (libsource (lib "eagle-import") (part "1711026"))
    )
    (comp (ref "R7")
      (value "200M")
      (footprint "eagle-import:R0805")
      (libsource (lib "eagle-import") (part "R-US_R0805"))
    )
    (comp (ref "R8")
      (value "13.3K")
      (footprint "eagle-import:R0805")
      (libsource (lib "eagle-import") (part "R-US_R0805"))
    )
    (comp (ref "R9")
      (value "7.5K")
      (footprint "eagle-import:R0805")
      (libsource (lib "eagle-import") (part "R-US_R0805"))
    )
    (comp (ref "R10")
      (value "200M")
      (footprint "eagle-import:R0805")
      (libsource (lib "eagle-import") (part "R-US_R0805"))
    )
    (comp (ref "R11")
      (value "13.3K")
      (footprint "eagle-import:R0805")
      (libsource (lib "eagle-import") (part "R-US_R0805"))
    )
    (comp (ref "R12")
      (value "7.5K")
      (footprint "eagle-import:R0805")
      (libsource (lib "eagle-import") (part "R-US_R0805"))
    )
    (comp (ref "C37")
      (value "10uF")
      (footprint "eagle-import:C0805")
      (libsource (lib "eagle-import") (part "C-USC0805"))
    )
    (comp (ref "C38")
      (value "10uF")
      (footprint "eagle-import:C0805")
      (libsource (lib "eagle-import") (part "C-USC0805"))
    )
    (comp (ref "C39")
      (value "0.1uF")
      (footprint "eagle-import:C0805")
      (libsource (lib "eagle-import") (part "C-USC0805"))
    )
    (comp (ref "C40")
      (value "10uF")
      (footprint "eagle-import:C0805")
      (libsource (lib "eagle-import") (part "C-USC0805"))
    )
    (comp (ref "C41")
      (value "10uF")
      (footprint "eagle-import:C0805")
      (libsource (lib "eagle-import") (part "C-USC0805"))
    )
    (comp (ref "C42")
      (value "0.1uF")
      (footprint "eagle-import:C0805")
      (libsource (lib "eagle-import") (part "C-USC0805"))
    )
    (comp (ref "IC21")
      (value "OPA1632DR")
      (footprint "eagle-import:SOIC127P600X175-8N")
      (fields (field (name "MOUSER_PART_NUMBER") "595-OPA1632DR"))
      (libsource (lib "eagle-import") (part "OPA1632DR"))
    )
    (comp (ref "IC22")
      (value "OPA1632DR")
      (footprint "eagle-import:SOIC127P600X175-8N")
      (fields (field (name "MOUSER_PART_NUMBER") "595-OPA1632DR"))
      (libsource (lib "eagle-import") (part "OPA1632DR"))
    )
    (comp (ref "R49")
      (value "1K")
      (footprint "eagle-import:R0805")
      (libsource (lib "eagle-import") (part "R-US_R0805"))
    )
    (comp (ref "R50")
      (value "249R")
      (footprint "eagle-import:R0805")
      (libsource (lib "eagle-import") (part "R-US_R0805"))
    )
    (comp (ref "R51")
      (value "49.9R")
      (footprint "eagle-import:R0805")
      (libsource (lib "eagle-import") (part "R-US_R0805"))
    )
    (comp (ref "R52")
      (value "249R")
      (footprint "eagle-import:R0805")
      (libsource (lib "eagle-import") (part "R-US_R0805"))
    )
    (comp (ref "R53")
      (value "49.9R")
      (footprint "eagle-import:R0805")
      (libsource (lib "eagle-import") (part "R-US_R0805"))
    )
    (comp (ref "R54")
      (value "1K")
      (footprint "eagle-import:R0805")
      (libsource (lib "eagle-import") (part "R-US_R0805"))
    )
    (comp (ref "R55")
      (value "1K")
      (footprint "eagle-import:R0805")
      (libsource (lib "eagle-import") (part "R-US_R0805"))
    )
    (comp (ref "R56")
      (value "249R")
      (footprint "eagle-import:R0805")
      (libsource (lib "eagle-import") (part "R-US_R0805"))
    )
    (comp (ref "R57")
      (value "49.9R")
      (footprint "eagle-import:R0805")
      (libsource (lib "eagle-import") (part "R-US_R0805"))
    )
    (comp (ref "R58")
      (value "249R")
      (footprint "eagle-import:R0805")
      (libsource (lib "eagle-import") (part "R-US_R0805"))
    )
    (comp (ref "R59")
      (value "49.9R")
      (footprint "eagle-import:R0805")
      (libsource (lib "eagle-import") (part "R-US_R0805"))
    )
    (comp (ref "R60")
      (value "1K")
      (footprint "eagle-import:R0805")
      (libsource (lib "eagle-import") (part "R-US_R0805"))
    )
    (comp (ref "C1")
      (value "20nF")
      (footprint "eagle-import:C0805")
      (libsource (lib "eagle-import") (part "C-USC0805"))
    )
    (comp (ref "C2")
      (value "18uF")
      (footprint "eagle-import:C0805")
      (libsource (lib "eagle-import") (part "C-USC0805"))
    )
    (comp (ref "C3")
      (value "39uF")
      (footprint "eagle-import:C0805")
      (libsource (lib "eagle-import") (part "C-USC0805"))
    )
    (comp (ref "C4")
      (value "20nF")
      (footprint "eagle-import:C0805")
      (libsource (lib "eagle-import") (part "C-USC0805"))
    )
    (comp (ref "C5")
      (value "18uF")
      (footprint "eagle-import:C0805")
      (libsource (lib "eagle-import") (part "C-USC0805"))
    )
    (comp (ref "C6")
      (value "39uF")
      (footprint "eagle-import:C0805")
      (libsource (lib "eagle-import") (part "C-USC0805"))
    )
    (comp (ref "IC1")
      (value "TLV2771CDBVR")
      (footprint "eagle-import:SOT95P280X145-5N")
      (fields (field (name "MOUSER_PART_NUMBER") "595-TLV2771CDBVR"))
      (libsource (lib "eagle-import") (part "TLV2771CDBVR"))
    )
    (comp (ref "IC2")
      (value "TLV2771CDBVR")
      (footprint "eagle-import:SOT95P280X145-5N")
      (fields (field (name "MOUSER_PART_NUMBER") "595-TLV2771CDBVR"))
      (libsource (lib "eagle-import") (part "TLV2771CDBVR"))
    )
    (comp (ref "IC3")
      (value "MCP601OT")
      (footprint "eagle-import:SOT23-5")
      (libsource (lib "eagle-import") (part "MCP601OT"))
    )
    (comp (ref "IC4")
      (value "MCP601OT")
      (footprint "eagle-import:SOT23-5")
      (libsource (lib "eagle-import") (part "MCP601OT"))
    )
    (comp (ref "J1")
      (value "1711026")
      (footprint "eagle-import:SHDR2W110P0X500_1X2_1000X1120X")
      (fields (field (name "MOUSER_PART_NUMBER") "651-1711026"))
      (libsource (lib "eagle-import") (part "1711026"))
    )
    (comp (ref "J2")
      (value "1711026")
      (footprint "eagle-import:SHDR2W110P0X500_1X2_1000X1120X")
      (fields (field (name "MOUSER_PART_NUMBER") "651-1711026"))
      (libsource (lib "eagle-import") (part "1711026"))
    )
    (comp (ref "R1")
      (value "200M")
      (footprint "eagle-import:R0805")
      (libsource (lib "eagle-import") (part "R-US_R0805"))
    )
    (comp (ref "R2")
      (value "13.3K")
      (footprint "eagle-import:R0805")
      (libsource (lib "eagle-import") (part "R-US_R0805"))
    )
    (comp (ref "R3")
      (value "7.5K")
      (footprint "eagle-import:R0805")
      (libsource (lib "eagle-import") (part "R-US_R0805"))
    )
    (comp (ref "R4")
      (value "200M")
      (footprint "eagle-import:R0805")
      (libsource (lib "eagle-import") (part "R-US_R0805"))
    )
    (comp (ref "R5")
      (value "13.3K")
      (footprint "eagle-import:R0805")
      (libsource (lib "eagle-import") (part "R-US_R0805"))
    )
    (comp (ref "R6")
      (value "7.5K")
      (footprint "eagle-import:R0805")
      (libsource (lib "eagle-import") (part "R-US_R0805"))
    )
    (comp (ref "C25")
      (value "10uF")
      (footprint "eagle-import:C0805")
      (libsource (lib "eagle-import") (part "C-USC0805"))
    )
    (comp (ref "C26")
      (value "10uF")
      (footprint "eagle-import:C0805")
      (libsource (lib "eagle-import") (part "C-USC0805"))
    )
    (comp (ref "C27")
      (value "0.1uF")
      (footprint "eagle-import:C0805")
      (libsource (lib "eagle-import") (part "C-USC0805"))
    )
    (comp (ref "C28")
      (value "10uF")
      (footprint "eagle-import:C0805")
      (libsource (lib "eagle-import") (part "C-USC0805"))
    )
    (comp (ref "C29")
      (value "10uF")
      (footprint "eagle-import:C0805")
      (libsource (lib "eagle-import") (part "C-USC0805"))
    )
    (comp (ref "C30")
      (value "0.1uF")
      (footprint "eagle-import:C0805")
      (libsource (lib "eagle-import") (part "C-USC0805"))
    )
    (comp (ref "IC17")
      (value "OPA1632DR")
      (footprint "eagle-import:SOIC127P600X175-8N")
      (fields (field (name "MOUSER_PART_NUMBER") "595-OPA1632DR"))
      (libsource (lib "eagle-import") (part "OPA1632DR"))
    )
    (comp (ref "IC18")
      (value "OPA1632DR")
      (footprint "eagle-import:SOIC127P600X175-8N")
      (fields (field (name "MOUSER_PART_NUMBER") "595-OPA1632DR"))
      (libsource (lib "eagle-import") (part "OPA1632DR"))
    )
    (comp (ref "R25")
      (value "1K")
      (footprint "eagle-import:R0805")
      (libsource (lib "eagle-import") (part "R-US_R0805"))
    )
    (comp (ref "R26")
      (value "249R")
      (footprint "eagle-import:R0805")
      (libsource (lib "eagle-import") (part "R-US_R0805"))
    )
    (comp (ref "R27")
      (value "49.9R")
      (footprint "eagle-import:R0805")
      (libsource (lib "eagle-import") (part "R-US_R0805"))
    )
    (comp (ref "R28")
      (value "249R")
      (footprint "eagle-import:R0805")
      (libsource (lib "eagle-import") (part "R-US_R0805"))
    )
    (comp (ref "R29")
      (value "49.9R")
      (footprint "eagle-import:R0805")
      (libsource (lib "eagle-import") (part "R-US_R0805"))
    )
    (comp (ref "R30")
      (value "1K")
      (footprint "eagle-import:R0805")
      (libsource (lib "eagle-import") (part "R-US_R0805"))
    )
    (comp (ref "R31")
      (value "1K")
      (footprint "eagle-import:R0805")
      (libsource (lib "eagle-import") (part "R-US_R0805"))
    )
    (comp (ref "R32")
      (value "249R")
      (footprint "eagle-import:R0805")
      (libsource (lib "eagle-import") (part "R-US_R0805"))
    )
    (comp (ref "R33")
      (value "49.9R")
      (footprint "eagle-import:R0805")
      (libsource (lib "eagle-import") (part "R-US_R0805"))
    )
    (comp (ref "R34")
      (value "249R")
      (footprint "eagle-import:R0805")
      (libsource (lib "eagle-import") (part "R-US_R0805"))
    )
    (comp (ref "R35")
      (value "49.9R")
      (footprint "eagle-import:R0805")
      (libsource (lib "eagle-import") (part "R-US_R0805"))
    )
    (comp (ref "R36")
      (value "1K")
      (footprint "eagle-import:R0805")
      (libsource (lib "eagle-import") (part "R-US_R0805"))
    )
    (comp (ref "C49")
      (value "100uF")
      (footprint "eagle-import:C0805")
      (libsource (lib "eagle-import") (part "C-USC0805"))
    )
    (comp (ref "C50")
      (value "0.1uF")
      (footprint "eagle-import:C0805")
      (libsource (lib "eagle-import") (part "C-USC0805"))
    )
    (comp (ref "C51")
      (value "0.1uF")
      (footprint "eagle-import:C0805")
      (libsource (lib "eagle-import") (part "C-USC0805"))
    )
    (comp (ref "C52")
      (value "10uF")
      (footprint "eagle-import:C0805")
      (libsource (lib "eagle-import") (part "C-USC0805"))
    )
    (comp (ref "C53")
      (value "0.1uF")
      (footprint "eagle-import:C0805")
      (libsource (lib "eagle-import") (part "C-USC0805"))
    )
    (comp (ref "C54")
      (value "0.1uF")
      (footprint "eagle-import:C0805")
      (libsource (lib "eagle-import") (part "C-USC0805"))
    )
    (comp (ref "C55")
      (value "2.2nF")
      (footprint "eagle-import:C0805")
      (libsource (lib "eagle-import") (part "C-USC0805"))
    )
    (comp (ref "C56")
      (value "2.2nF")
      (footprint "eagle-import:C0805")
      (libsource (lib "eagle-import") (part "C-USC0805"))
    )
    (comp (ref "C57")
      (value "2.2nF")
      (footprint "eagle-import:C0805")
      (libsource (lib "eagle-import") (part "C-USC0805"))
    )
    (comp (ref "C58")
      (value "2.2nF")
      (footprint "eagle-import:C0805")
      (libsource (lib "eagle-import") (part "C-USC0805"))
    )
    (comp (ref "C59")
      (value "2.2nF")
      (footprint "eagle-import:C0805")
      (libsource (lib "eagle-import") (part "C-USC0805"))
    )
    (comp (ref "C60")
      (value "2.2nF")
      (footprint "eagle-import:C0805")
      (libsource (lib "eagle-import") (part "C-USC0805"))
    )
    (comp (ref "C61")
      (value "2.2nF")
      (footprint "eagle-import:C0805")
      (libsource (lib "eagle-import") (part "C-USC0805"))
    )
    (comp (ref "C62")
      (value "2.2nF")
      (footprint "eagle-import:C0805")
      (libsource (lib "eagle-import") (part "C-USC0805"))
    )
    (comp (ref "IC25")
      (value "REF1004U")
      (footprint "eagle-import:SO08")
      (fields (field (name "MF") "TEXAS INSTRUMENTS") (field (name "MPN") "REF1004C-1.2"))
      (libsource (lib "eagle-import") (part "REF1004U"))
    )
    (comp (ref "R73")
      (value "20K")
      (footprint "eagle-import:R0805")
      (libsource (lib "eagle-import") (part "R-US_R0805"))
    )
    (comp (ref "R74")
      (value "1K")
      (footprint "eagle-import:R0805")
      (libsource (lib "eagle-import") (part "R-US_R0805"))
    )
    (comp (ref "R75")
      (value "100R")
      (footprint "eagle-import:R0805")
      (libsource (lib "eagle-import") (part "R-US_R0805"))
    )
    (comp (ref "R76")
      (value "1K")
      (footprint "eagle-import:R0805")
      (libsource (lib "eagle-import") (part "R-US_R0805"))
    )
    (comp (ref "R77")
      (value "100R")
      (footprint "eagle-import:R0805")
      (libsource (lib "eagle-import") (part "R-US_R0805"))
    )
    (comp (ref "R78")
      (value "100R")
      (footprint "eagle-import:R0805")
      (libsource (lib "eagle-import") (part "R-US_R0805"))
    )
    (comp (ref "U1")
      (value "OPA350EA/2K5")
      (footprint "eagle-import:DGK8_TEX")
      (fields
        (field (name "MANUFACTURER") "Texas Instruments")
        (field (name "COPYRIGHT") "Copyright (C) 2018 Accelerated Designs. All rights reserved")
      )
      (libsource (lib "eagle-import") (part "OPA350EA/2K5"))
    )
    (comp (ref "U2")
      (value "OPA350EA/2K5")
      (footprint "eagle-import:DGK8_TEX")
      (fields
        (field (name "MANUFACTURER") "Texas Instruments")
        (field (name "COPYRIGHT") "Copyright (C) 2018 Accelerated Designs. All rights reserved")
      )
      (libsource (lib "eagle-import") (part "OPA350EA/2K5"))
    )
  )
  (nets
    (net (code "1") (name "+1V8") (class "Default")
      (node (ref "C65") (pin "1") (pinfunction "1_1") (pintype "passive"))
      (node (ref "JP1") (pin "19") (pinfunction "19_19") (pintype "passive"))
      (node (ref "JP1") (pin "20") (pinfunction "20_20") (pintype "passive"))
      (node (ref "U3") (pin "26") (pinfunction "DVDD_26") (pintype "power_in"))
    )
    (net (code "2") (name "+3V3") (class "Default")
      (node (ref "C64") (pin "1") (pinfunction "1_1") (pintype "passive"))
      (node (ref "JP1") (pin "17") (pinfunction "17_17") (pintype "passive"))
      (node (ref "JP1") (pin "18") (pinfunction "18_18") (pintype "passive"))
      (node (ref "SJ1") (pin "1") (pinfunction "1_1") (pintype "passive"))
      (node (ref "U3") (pin "10") (pinfunction "CLKDIV_10") (pintype "input"))
      (node (ref "U3") (pin "22") (pinfunction "IOVDD_2_22") (pintype "power_in"))
      (node (ref "U3") (pin "23") (pinfunction "IOVDD_23") (pintype "power_in"))
      (node (ref "U3") (pin "31") (pinfunction "FORMAT1_31") (pintype "input"))
    )
    (net (code "3") (name "+5V") (class "Default")
      (node (ref "C63") (pin "1") (pinfunction "1_1") (pintype "passive"))
      (node (ref "IC1") (pin "5") (pinfunction "VDD_5") (pintype "bidirectional"))
      (node (ref "IC10") (pin "5") (pinfunction "V+_5") (pintype "power_in"))
      (node (ref "IC11") (pin "5") (pinfunction "VDD_5") (pintype "bidirectional"))
      (node (ref "IC12") (pin "5") (pinfunction "V+_5") (pintype "power_in"))
      (node (ref "IC13") (pin "5") (pinfunction "VDD_5") (pintype "bidirectional"))
      (node (ref "IC14") (pin "5") (pinfunction "V+_5") (pintype "power_in"))
      (node (ref "IC15") (pin "5") (pinfunction "VDD_5") (pintype "bidirectional"))
      (node (ref "IC16") (pin "5") (pinfunction "V+_5") (pintype "power_in"))
      (node (ref "IC2") (pin "5") (pinfunction "VDD_5") (pintype "bidirectional"))
      (node (ref "IC3") (pin "5") (pinfunction "V+_5") (pintype "power_in"))
      (node (ref "IC4") (pin "5") (pinfunction "V+_5") (pintype "power_in"))
      (node (ref "IC5") (pin "5") (pinfunction "VDD_5") (pintype "bidirectional"))
      (node (ref "IC6") (pin "5") (pinfunction "V+_5") (pintype "power_in"))
      (node (ref "IC7") (pin "5") (pinfunction "VDD_5") (pintype "bidirectional"))
      (node (ref "IC8") (pin "5") (pinfunction "V+_5") (pintype "power_in"))
      (node (ref "IC9") (pin "5") (pinfunction "VDD_5") (pintype "bidirectional"))
      (node (ref "JP1") (pin "13") (pinfunction "13_13") (pintype "passive"))
      (node (ref "JP1") (pin "14") (pinfunction "14_14") (pintype "passive"))
      (node (ref "R73") (pin "2") (pinfunction "2_2") (pintype "passive"))
      (node (ref "U1") (pin "7") (pinfunction "V+_7") (pintype "power_in"))
      (node (ref "U2") (pin "7") (pinfunction "V+_7") (pintype "power_in"))
      (node (ref "U3") (pin "44") (pinfunction "AVDD_3_44") (pintype "power_in"))
      (node (ref "U3") (pin "5") (pinfunction "AVDD_2_5") (pintype "power_in"))
      (node (ref "U3") (pin "60") (pinfunction "AVDD_60") (pintype "power_in"))
    )
    (net (code "4") (name "+12V") (class "Default")
      (node (ref "IC17") (pin "3") (pinfunction "V+_3") (pintype "bidirectional"))
      (node (ref "IC18") (pin "3") (pinfunction "V+_3") (pintype "bidirectional"))
      (node (ref "IC19") (pin "3") (pinfunction "V+_3") (pintype "bidirectional"))
      (node (ref "IC20") (pin "3") (pinfunction "V+_3") (pintype "bidirectional"))
      (node (ref "IC21") (pin "3") (pinfunction "V+_3") (pintype "bidirectional"))
      (node (ref "IC22") (pin "3") (pinfunction "V+_3") (pintype "bidirectional"))
      (node (ref "IC23") (pin "3") (pinfunction "V+_3") (pintype "bidirectional"))
      (node (ref "IC24") (pin "3") (pinfunction "V+_3") (pintype "bidirectional"))
      (node (ref "JP1") (pin "1") (pinfunction "1_1") (pintype "passive"))
      (node (ref "JP1") (pin "2") (pinfunction "2_2") (pintype "passive"))
    )
    (net (code "5") (name "+24V") (class "Default")
      (node (ref "JP1") (pin "10") (pinfunction "10_10") (pintype "passive"))
      (node (ref "JP1") (pin "9") (pinfunction "9_9") (pintype "passive"))
    )
    (net (code "6") (name "-12V") (class "Default")
      (node (ref "IC17") (pin "6") (pinfunction "V-_6") (pintype "bidirectional"))
      (node (ref "IC18") (pin "6") (pinfunction "V-_6") (pintype "bidirectional"))
      (node (ref "IC19") (pin "6") (pinfunction "V-_6") (pintype "bidirectional"))
      (node (ref "IC20") (pin "6") (pinfunction "V-_6") (pintype "bidirectional"))
      (node (ref "IC21") (pin "6") (pinfunction "V-_6") (pintype "bidirectional"))
      (node (ref "IC22") (pin "6") (pinfunction "V-_6") (pintype "bidirectional"))
      (node (ref "IC23") (pin "6") (pinfunction "V-_6") (pintype "bidirectional"))
      (node (ref "IC24") (pin "6") (pinfunction "V-_6") (pintype "bidirectional"))
      (node (ref "JP1") (pin "5") (pinfunction "5_5") (pintype "passive"))
      (node (ref "JP1") (pin "6") (pinfunction "6_6") (pintype "passive"))
    )
    (net (code "7") (name "AINN1") (class "Default")
      (node (ref "C55") (pin "2") (pinfunction "2_2") (pintype "passive"))
      (node (ref "R34") (pin "1") (pinfunction "1_1") (pintype "passive"))
      (node (ref "R35") (pin "1") (pinfunction "1_1") (pintype "passive"))
      (node (ref "U3") (pin "4") (pinfunction "AINN1_4") (pintype "input"))
    )
    (net (code "8") (name "AINN2") (class "Default")
      (node (ref "C56") (pin "2") (pinfunction "2_2") (pintype "passive"))
      (node (ref "R52") (pin "1") (pinfunction "1_1") (pintype "passive"))
      (node (ref "R53") (pin "1") (pinfunction "1_1") (pintype "passive"))
      (node (ref "U3") (pin "2") (pinfunction "AINN2_2") (pintype "input"))
    )
    (net (code "9") (name "AINN3") (class "Default")
      (node (ref "C57") (pin "2") (pinfunction "2_2") (pintype "passive"))
      (node (ref "R40") (pin "1") (pinfunction "1_1") (pintype "passive"))
      (node (ref "R41") (pin "1") (pinfunction "1_1") (pintype "passive"))
      (node (ref "U3") (pin "64") (pinfunction "AINN3_64") (pintype "input"))
    )
    (net (code "10") (name "AINN4") (class "Default")
      (node (ref "C58") (pin "2") (pinfunction "2_2") (pintype "passive"))
      (node (ref "R46") (pin "1") (pinfunction "1_1") (pintype "passive"))
      (node (ref "R47") (pin "1") (pinfunction "1_1") (pintype "passive"))
      (node (ref "U3") (pin "62") (pinfunction "AINN4_62") (pintype "input"))
    )
    (net (code "11") (name "AINN5") (class "Default")
      (node (ref "C59") (pin "2") (pinfunction "2_2") (pintype "passive"))
      (node (ref "R28") (pin "1") (pinfunction "1_1") (pintype "passive"))
      (node (ref "R29") (pin "1") (pinfunction "1_1") (pintype "passive"))
      (node (ref "U3") (pin "52") (pinfunction "AINN5_52") (pintype "input"))
    )
    (net (code "12") (name "AINN6") (class "Default")
      (node (ref "C60") (pin "2") (pinfunction "2_2") (pintype "passive"))
      (node (ref "R70") (pin "1") (pinfunction "1_1") (pintype "passive"))
      (node (ref "R71") (pin "1") (pinfunction "1_1") (pintype "passive"))
      (node (ref "U3") (pin "50") (pinfunction "AINN6_50") (pintype "input"))
    )
    (net (code "13") (name "AINN7") (class "Default")
      (node (ref "C61") (pin "2") (pinfunction "2_2") (pintype "passive"))
      (node (ref "R64") (pin "1") (pinfunction "1_1") (pintype "passive"))
      (node (ref "R65") (pin "1") (pinfunction "1_1") (pintype "passive"))
      (node (ref "U3") (pin "48") (pinfunction "AINN7_48") (pintype "input"))
    )
    (net (code "14") (name "AINN8") (class "Default")
      (node (ref "C62") (pin "2") (pinfunction "2_2") (pintype "passive"))
      (node (ref "R58") (pin "1") (pinfunction "1_1") (pintype "passive"))
      (node (ref "R59") (pin "1") (pinfunction "1_1") (pintype "passive"))
      (node (ref "U3") (pin "46") (pinfunction "AINN8_46") (pintype "input"))
    )
    (net (code "15") (name "AINP1") (class "Default")
      (node (ref "C55") (pin "1") (pinfunction "1_1") (pintype "passive"))
      (node (ref "R32") (pin "2") (pinfunction "2_2") (pintype "passive"))
      (node (ref "R33") (pin "2") (pinfunction "2_2") (pintype "passive"))
      (node (ref "U3") (pin "3") (pinfunction "AINP1_3") (pintype "input"))
    )
    (net (code "16") (name "AINP2") (class "Default")
      (node (ref "C56") (pin "1") (pinfunction "1_1") (pintype "passive"))
      (node (ref "R50") (pin "2") (pinfunction "2_2") (pintype "passive"))
      (node (ref "R51") (pin "2") (pinfunction "2_2") (pintype "passive"))
      (node (ref "U3") (pin "1") (pinfunction "AINP2_1") (pintype "input"))
    )
    (net (code "17") (name "AINP3") (class "Default")
      (node (ref "C57") (pin "1") (pinfunction "1_1") (pintype "passive"))
      (node (ref "R38") (pin "2") (pinfunction "2_2") (pintype "passive"))
      (node (ref "R39") (pin "2") (pinfunction "2_2") (pintype "passive"))
      (node (ref "U3") (pin "63") (pinfunction "AINP3_63") (pintype "input"))
    )
    (net (code "18") (name "AINP4") (class "Default")
      (node (ref "C58") (pin "1") (pinfunction "1_1") (pintype "passive"))
      (node (ref "R44") (pin "2") (pinfunction "2_2") (pintype "passive"))
      (node (ref "R45") (pin "2") (pinfunction "2_2") (pintype "passive"))
      (node (ref "U3") (pin "61") (pinfunction "AINP4_61") (pintype "input"))
    )
    (net (code "19") (name "AINP5") (class "Default")
      (node (ref "C59") (pin "1") (pinfunction "1_1") (pintype "passive"))
      (node (ref "R26") (pin "2") (pinfunction "2_2") (pintype "passive"))
      (node (ref "R27") (pin "2") (pinfunction "2_2") (pintype "passive"))
      (node (ref "U3") (pin "51") (pinfunction "AINP5_51") (pintype "input"))
    )
    (net (code "20") (name "AINP6") (class "Default")
      (node (ref "C60") (pin "1") (pinfunction "1_1") (pintype "passive"))
      (node (ref "R68") (pin "2") (pinfunction "2_2") (pintype "passive"))
      (node (ref "R69") (pin "2") (pinfunction "2_2") (pintype "passive"))
      (node (ref "U3") (pin "49") (pinfunction "AINP6_49") (pintype "input"))
    )
    (net (code "21") (name "AINP7") (class "Default")
      (node (ref "C61") (pin "1") (pinfunction "1_1") (pintype "passive"))
      (node (ref "R62") (pin "2") (pinfunction "2_2") (pintype "passive"))
      (node (ref "R63") (pin "2") (pinfunction "2_2") (pintype "passive"))
      (node (ref "U3") (pin "47") (pinfunction "AINP7_47") (pintype "input"))
    )
    (net (code "22") (name "AINP8") (class "Default")
      (node (ref "C62") (pin "1") (pinfunction "1_1") (pintype "passive"))
      (node (ref "R56") (pin "2") (pinfunction "2_2") (pintype "passive"))
      (node (ref "R57") (pin "2") (pinfunction "2_2") (pintype "passive"))
      (node (ref "U3") (pin "45") (pinfunction "AINP8_45") (pintype "input"))
    )
    (net (code "23") (name "CLK") (class "Default")
      (node (ref "JP2") (pin "9") (pinfunction "9_9") (pintype "passive"))
      (node (ref "U3") (pin "27") (pinfunction "CLK_27") (pintype "input"))
    )
    (net (code "24") (name "DOUT1") (class "Default")
      (node (ref "JP2") (pin "10") (pinfunction "10_10") (pintype "passive"))
      (node (ref "U3") (pin "20") (pinfunction "DOUT1_20") (pintype "output"))
    )
    (net (code "25") (name "DOUT2") (class "Default")
      (node (ref "JP2") (pin "7") (pinfunction "7_7") (pintype "passive"))
      (node (ref "U3") (pin "19") (pinfunction "DOUT2_19") (pintype "output"))
    )
    (net (code "26") (name "DOUT3") (class "Default")
      (node (ref "JP2") (pin "8") (pinfunction "8_8") (pintype "passive"))
      (node (ref "U3") (pin "18") (pinfunction "DOUT3_18") (pintype "output"))
    )
    (net (code "27") (name "DOUT4") (class "Default")
      (node (ref "JP2") (pin "5") (pinfunction "5_5") (pintype "passive"))
      (node (ref "U3") (pin "17") (pinfunction "DOUT4_17") (pintype "output"))
    )
    (net (code "28") (name "DOUT5") (class "Default")
      (node (ref "JP2") (pin "6") (pinfunction "6_6") (pintype "passive"))
      (node (ref "U3") (pin "16") (pinfunction "DOUT5_16") (pintype "output"))
    )
    (net (code "29") (name "DOUT6") (class "Default")
      (node (ref "JP2") (pin "3") (pinfunction "3_3") (pintype "passive"))
      (node (ref "U3") (pin "15") (pinfunction "DOUT6_15") (pintype "output"))
    )
    (net (code "30") (name "DOUT7") (class "Default")
      (node (ref "JP2") (pin "4") (pinfunction "4_4") (pintype "passive"))
      (node (ref "U3") (pin "14") (pinfunction "DOUT7_14") (pintype "output"))
    )
    (net (code "31") (name "DOUT8") (class "Default")
      (node (ref "JP2") (pin "1") (pinfunction "1_1") (pintype "passive"))
      (node (ref "U3") (pin "13") (pinfunction "DOUT8_13") (pintype "output"))
    )
    (net (code "32") (name "DRDY") (class "Default")
      (node (ref "JP2") (pin "11") (pinfunction "11_11") (pintype "passive"))
      (node (ref "U3") (pin "29") (pinfunction "~{DRDY/FSYNC}_29") (pintype "bidirectional"))
    )
    (net (code "33") (name "GND") (class "Default")
      (node (ref "C11") (pin "2") (pinfunction "2_2") (pintype "passive"))
      (node (ref "C14") (pin "2") (pinfunction "2_2") (pintype "passive"))
      (node (ref "C17") (pin "2") (pinfunction "2_2") (pintype "passive"))
      (node (ref "C2") (pin "2") (pinfunction "2_2") (pintype "passive"))
      (node (ref "C20") (pin "2") (pinfunction "2_2") (pintype "passive"))
      (node (ref "C23") (pin "2") (pinfunction "2_2") (pintype "passive"))
      (node (ref "C27") (pin "2") (pinfunction "2_2") (pintype "passive"))
      (node (ref "C30") (pin "2") (pinfunction "2_2") (pintype "passive"))
      (node (ref "C33") (pin "2") (pinfunction "2_2") (pintype "passive"))
      (node (ref "C36") (pin "2") (pinfunction "2_2") (pintype "passive"))
      (node (ref "C39") (pin "2") (pinfunction "2_2") (pintype "passive"))
      (node (ref "C42") (pin "2") (pinfunction "2_2") (pintype "passive"))
      (node (ref "C45") (pin "2") (pinfunction "2_2") (pintype "passive"))
      (node (ref "C48") (pin "2") (pinfunction "2_2") (pintype "passive"))
      (node (ref "C49") (pin "2") (pinfunction "2_2") (pintype "passive"))
      (node (ref "C5") (pin "2") (pinfunction "2_2") (pintype "passive"))
      (node (ref "C50") (pin "2") (pinfunction "2_2") (pintype "passive"))
      (node (ref "C52") (pin "2") (pinfunction "2_2") (pintype "passive"))
      (node (ref "C53") (pin "2") (pinfunction "2_2") (pintype "passive"))
      (node (ref "C54") (pin "2") (pinfunction "2_2") (pintype "passive"))
      (node (ref "C63") (pin "2") (pinfunction "2_2") (pintype "passive"))
      (node (ref "C64") (pin "2") (pinfunction "2_2") (pintype "passive"))
      (node (ref "C65") (pin "2") (pinfunction "2_2") (pintype "passive"))
      (node (ref "C8") (pin "2") (pinfunction "2_2") (pintype "passive"))
      (node (ref "IC1") (pin "2") (pinfunction "GND_2") (pintype "bidirectional"))
      (node (ref "IC1") (pin "3") (pinfunction "IN+_3") (pintype "bidirectional"))
      (node (ref "IC10") (pin "2") (pinfunction "V-_2") (pintype "power_in"))
      (node (ref "IC11") (pin "2") (pinfunction "GND_2") (pintype "bidirectional"))
      (node (ref "IC11") (pin "3") (pinfunction "IN+_3") (pintype "bidirectional"))
      (node (ref "IC12") (pin "2") (pinfunction "V-_2") (pintype "power_in"))
      (node (ref "IC13") (pin "2") (pinfunction "GND_2") (pintype "bidirectional"))
      (node (ref "IC13") (pin "3") (pinfunction "IN+_3") (pintype "bidirectional"))
      (node (ref "IC14") (pin "2") (pinfunction "V-_2") (pintype "power_in"))
      (node (ref "IC15") (pin "2") (pinfunction "GND_2") (pintype "bidirectional"))
      (node (ref "IC15") (pin "3") (pinfunction "IN+_3") (pintype "bidirectional"))
      (node (ref "IC16") (pin "2") (pinfunction "V-_2") (pintype "power_in"))
      (node (ref "IC2") (pin "2") (pinfunction "GND_2") (pintype "bidirectional"))
      (node (ref "IC2") (pin "3") (pinfunction "IN+_3") (pintype "bidirectional"))
      (node (ref "IC25") (pin "4") (pinfunction "A_4") (pintype "passive"))
      (node (ref "IC3") (pin "2") (pinfunction "V-_2") (pintype "power_in"))
      (node (ref "IC4") (pin "2") (pinfunction "V-_2") (pintype "power_in"))
      (node (ref "IC5") (pin "2") (pinfunction "GND_2") (pintype "bidirectional"))
      (node (ref "IC5") (pin "3") (pinfunction "IN+_3") (pintype "bidirectional"))
      (node (ref "IC6") (pin "2") (pinfunction "V-_2") (pintype "power_in"))
      (node (ref "IC7") (pin "2") (pinfunction "GND_2") (pintype "bidirectional"))
      (node (ref "IC7") (pin "3") (pinfunction "IN+_3") (pintype "bidirectional"))
      (node (ref "IC8") (pin "2") (pinfunction "V-_2") (pintype "power_in"))
      (node (ref "IC9") (pin "2") (pinfunction "GND_2") (pintype "bidirectional"))
      (node (ref "IC9") (pin "3") (pinfunction "IN+_3") (pintype "bidirectional"))
      (node (ref "J1") (pin "2") (pinfunction "2_2") (pintype "bidirectional"))
      (node (ref "J2") (pin "2") (pinfunction "2_2") (pintype "bidirectional"))
      (node (ref "J3") (pin "2") (pinfunction "2_2") (pintype "bidirectional"))
      (node (ref "J4") (pin "2") (pinfunction "2_2") (pintype "bidirectional"))
      (node (ref "J5") (pin "2") (pinfunction "2_2") (pintype "bidirectional"))
      (node (ref "J6") (pin "2") (pinfunction "2_2") (pintype "bidirectional"))
      (node (ref "J7") (pin "2") (pinfunction "2_2") (pintype "bidirectional"))
      (node (ref "J8") (pin "2") (pinfunction "2_2") (pintype "bidirectional"))
      (node (ref "JP1") (pin "11") (pinfunction "11_11") (pintype "passive"))
      (node (ref "JP1") (pin "12") (pinfunction "12_12") (pintype "passive"))
      (node (ref "JP1") (pin "15") (pinfunction "15_15") (pintype "passive"))
      (node (ref "JP1") (pin "16") (pinfunction "16_16") (pintype "passive"))
      (node (ref "JP1") (pin "3") (pinfunction "3_3") (pintype "passive"))
      (node (ref "JP1") (pin "4") (pinfunction "4_4") (pintype "passive"))
      (node (ref "JP1") (pin "7") (pinfunction "7_7") (pintype "passive"))
      (node (ref "JP1") (pin "8") (pinfunction "8_8") (pintype "passive"))
      (node (ref "JP2") (pin "13") (pinfunction "13_13") (pintype "passive"))
      (node (ref "JP2") (pin "14") (pinfunction "14_14") (pintype "passive"))
      (node (ref "JP2") (pin "15") (pinfunction "15_15") (pintype "passive"))
      (node (ref "JP2") (pin "16") (pinfunction "16_16") (pintype "passive"))
      (node (ref "JP2") (pin "17") (pinfunction "17_17") (pintype "passive"))
      (node (ref "JP2") (pin "18") (pinfunction "18_18") (pintype "passive"))
      (node (ref "JP2") (pin "19") (pinfunction "19_19") (pintype "passive"))
      (node (ref "JP2") (pin "20") (pinfunction "20_20") (pintype "passive"))
      (node (ref "R30") (pin "2") (pinfunction "2_2") (pintype "passive"))
      (node (ref "R36") (pin "2") (pinfunction "2_2") (pintype "passive"))
      (node (ref "R42") (pin "2") (pinfunction "2_2") (pintype "passive"))
      (node (ref "R48") (pin "2") (pinfunction "2_2") (pintype "passive"))
      (node (ref "R54") (pin "2") (pinfunction "2_2") (pintype "passive"))
      (node (ref "R60") (pin "2") (pinfunction "2_2") (pintype "passive"))
      (node (ref "R66") (pin "2") (pinfunction "2_2") (pintype "passive"))
      (node (ref "R72") (pin "2") (pinfunction "2_2") (pintype "passive"))
      (node (ref "SJ1") (pin "3") (pinfunction "3_3") (pintype "passive"))
      (node (ref "U1") (pin "4") (pinfunction "V-_4") (pintype "power_in"))
      (node (ref "U2") (pin "4") (pinfunction "V-_4") (pintype "power_in"))
      (node (ref "U3") (pin "12") (pinfunction "DIN_12") (pintype "input"))
      (node (ref "U3") (pin "21") (pinfunction "DGND_3_21") (pintype "power_in"))
      (node (ref "U3") (pin "24") (pinfunction "DGND_4_24") (pintype "power_in"))
      (node (ref "U3") (pin "25") (pinfunction "DGND_25") (pintype "power_in"))
      (node (ref "U3") (pin "30") (pinfunction "FORMAT2_30") (pintype "input"))
      (node (ref "U3") (pin "32") (pinfunction "FORMAT0_32") (pintype "input"))
      (node (ref "U3") (pin "34") (pinfunction "MODE_34") (pintype "input"))
      (node (ref "U3") (pin "43") (pinfunction "AGND_3_43") (pintype "power_in"))
      (node (ref "U3") (pin "53") (pinfunction "AVDD_4_53") (pintype "power_in"))
      (node (ref "U3") (pin "54") (pinfunction "AGND_4_54") (pintype "power_in"))
      (node (ref "U3") (pin "57") (pinfunction "VREFN_57") (pintype "power_in"))
      (node (ref "U3") (pin "58") (pinfunction "AGND_5_58") (pintype "power_in"))
      (node (ref "U3") (pin "59") (pinfunction "AGND_59") (pintype "power_in"))
      (node (ref "U3") (pin "6") (pinfunction "AGND_2_6") (pintype "power_in"))
      (node (ref "U3") (pin "7") (pinfunction "DGND_2_7") (pintype "power_in"))
      (node (ref "U3") (pin "8") (pinfunction "TEST0_8") (pintype "input"))
      (node (ref "U3") (pin "9") (pinfunction "TEST1_9") (pintype "input"))
      (node (ref "U3") (pin "EPAD") (pinfunction "EPAD_EPAD") (pintype "passive"))
    )
    (net (code "34") (name "Net-(C3-Pad1)") (class "Default")
      (node (ref "C3") (pin "1") (pinfunction "1_1") (pintype "passive"))
      (node (ref "R2") (pin "1") (pinfunction "1_1") (pintype "passive"))
      (node (ref "R3") (pin "2") (pinfunction "2_2") (pintype "passive"))
    )
    (net (code "35") (name "Net-(C6-Pad1)") (class "Default")
      (node (ref "C6") (pin "1") (pinfunction "1_1") (pintype "passive"))
      (node (ref "R5") (pin "1") (pinfunction "1_1") (pintype "passive"))
      (node (ref "R6") (pin "2") (pinfunction "2_2") (pintype "passive"))
    )
    (net (code "36") (name "Net-(C9-Pad1)") (class "Default")
      (node (ref "C9") (pin "1") (pinfunction "1_1") (pintype "passive"))
      (node (ref "R8") (pin "1") (pinfunction "1_1") (pintype "passive"))
      (node (ref "R9") (pin "2") (pinfunction "2_2") (pintype "passive"))
    )
    (net (code "37") (name "Net-(C12-Pad1)") (class "Default")
      (node (ref "C12") (pin "1") (pinfunction "1_1") (pintype "passive"))
      (node (ref "R11") (pin "1") (pinfunction "1_1") (pintype "passive"))
      (node (ref "R12") (pin "2") (pinfunction "2_2") (pintype "passive"))
    )
    (net (code "38") (name "Net-(C15-Pad1)") (class "Default")
      (node (ref "C15") (pin "1") (pinfunction "1_1") (pintype "passive"))
      (node (ref "R14") (pin "1") (pinfunction "1_1") (pintype "passive"))
      (node (ref "R15") (pin "2") (pinfunction "2_2") (pintype "passive"))
    )
    (net (code "39") (name "Net-(C18-Pad1)") (class "Default")
      (node (ref "C18") (pin "1") (pinfunction "1_1") (pintype "passive"))
      (node (ref "R17") (pin "1") (pinfunction "1_1") (pintype "passive"))
      (node (ref "R18") (pin "2") (pinfunction "2_2") (pintype "passive"))
    )
    (net (code "40") (name "Net-(C21-Pad1)") (class "Default")
      (node (ref "C21") (pin "1") (pinfunction "1_1") (pintype "passive"))
      (node (ref "R20") (pin "1") (pinfunction "1_1") (pintype "passive"))
      (node (ref "R21") (pin "2") (pinfunction "2_2") (pintype "passive"))
    )
    (net (code "41") (name "Net-(C24-Pad1)") (class "Default")
      (node (ref "C24") (pin "1") (pinfunction "1_1") (pintype "passive"))
      (node (ref "R23") (pin "1") (pinfunction "1_1") (pintype "passive"))
      (node (ref "R24") (pin "2") (pinfunction "2_2") (pintype "passive"))
    )
    (net (code "42") (name "Net-(C49-Pad1)") (class "Default")
      (node (ref "C49") (pin "1") (pinfunction "1_1") (pintype "passive"))
      (node (ref "C50") (pin "1") (pinfunction "1_1") (pintype "passive"))
      (node (ref "R74") (pin "2") (pinfunction "2_2") (pintype "passive"))
      (node (ref "R75") (pin "1") (pinfunction "1_1") (pintype "passive"))
    )
    (net (code "43") (name "Net-(IC1-IN-)") (class "Default")
      (node (ref "C1") (pin "1") (pinfunction "1_1") (pintype "passive"))
      (node (ref "IC1") (pin "4") (pinfunction "IN-_4") (pintype "bidirectional"))
      (node (ref "J1") (pin "1") (pinfunction "1_1") (pintype "bidirectional"))
      (node (ref "R1") (pin "1") (pinfunction "1_1") (pintype "passive"))
    )
    (net (code "44") (name "Net-(IC1-OUT)") (class "Default")
      (node (ref "C1") (pin "2") (pinfunction "2_2") (pintype "passive"))
      (node (ref "IC1") (pin "1") (pinfunction "OUT_1") (pintype "bidirectional"))
      (node (ref "R1") (pin "2") (pinfunction "2_2") (pintype "passive"))
      (node (ref "R3") (pin "1") (pinfunction "1_1") (pintype "passive"))
    )
    (net (code "45") (name "Net-(IC2-IN-)") (class "Default")
      (node (ref "C4") (pin "1") (pinfunction "1_1") (pintype "passive"))
      (node (ref "IC2") (pin "4") (pinfunction "IN-_4") (pintype "bidirectional"))
      (node (ref "J2") (pin "1") (pinfunction "1_1") (pintype "bidirectional"))
      (node (ref "R4") (pin "1") (pinfunction "1_1") (pintype "passive"))
    )
    (net (code "46") (name "Net-(IC2-OUT)") (class "Default")
      (node (ref "C4") (pin "2") (pinfunction "2_2") (pintype "passive"))
      (node (ref "IC2") (pin "1") (pinfunction "OUT_1") (pintype "bidirectional"))
      (node (ref "R4") (pin "2") (pinfunction "2_2") (pintype "passive"))
      (node (ref "R6") (pin "1") (pinfunction "1_1") (pintype "passive"))
    )
    (net (code "47") (name "Net-(IC3-+IN)") (class "Default")
      (node (ref "C2") (pin "1") (pinfunction "1_1") (pintype "passive"))
      (node (ref "IC3") (pin "3") (pinfunction "+IN_3") (pintype "input"))
      (node (ref "R2") (pin "2") (pinfunction "2_2") (pintype "passive"))
    )
    (net (code "48") (name "Net-(IC4-+IN)") (class "Default")
      (node (ref "C5") (pin "1") (pinfunction "1_1") (pintype "passive"))
      (node (ref "IC4") (pin "3") (pinfunction "+IN_3") (pintype "input"))
      (node (ref "R5") (pin "2") (pinfunction "2_2") (pintype "passive"))
    )
    (net (code "49") (name "Net-(IC5-IN-)") (class "Default")
      (node (ref "C7") (pin "1") (pinfunction "1_1") (pintype "passive"))
      (node (ref "IC5") (pin "4") (pinfunction "IN-_4") (pintype "bidirectional"))
      (node (ref "J3") (pin "1") (pinfunction "1_1") (pintype "bidirectional"))
      (node (ref "R7") (pin "1") (pinfunction "1_1") (pintype "passive"))
    )
    (net (code "50") (name "Net-(IC5-OUT)") (class "Default")
      (node (ref "C7") (pin "2") (pinfunction "2_2") (pintype "passive"))
      (node (ref "IC5") (pin "1") (pinfunction "OUT_1") (pintype "bidirectional"))
      (node (ref "R7") (pin "2") (pinfunction "2_2") (pintype "passive"))
      (node (ref "R9") (pin "1") (pinfunction "1_1") (pintype "passive"))
    )
    (net (code "51") (name "Net-(IC6-+IN)") (class "Default")
      (node (ref "C8") (pin "1") (pinfunction "1_1") (pintype "passive"))
      (node (ref "IC6") (pin "3") (pinfunction "+IN_3") (pintype "input"))
      (node (ref "R8") (pin "2") (pinfunction "2_2") (pintype "passive"))
    )
    (net (code "52") (name "Net-(IC7-IN-)") (class "Default")
      (node (ref "C10") (pin "1") (pinfunction "1_1") (pintype "passive"))
      (node (ref "IC7") (pin "4") (pinfunction "IN-_4") (pintype "bidirectional"))
      (node (ref "J4") (pin "1") (pinfunction "1_1") (pintype "bidirectional"))
      (node (ref "R10") (pin "1") (pinfunction "1_1") (pintype "passive"))
    )
    (net (code "53") (name "Net-(IC7-OUT)") (class "Default")
      (node (ref "C10") (pin "2") (pinfunction "2_2") (pintype "passive"))
      (node (ref "IC7") (pin "1") (pinfunction "OUT_1") (pintype "bidirectional"))
      (node (ref "R10") (pin "2") (pinfunction "2_2") (pintype "passive"))
      (node (ref "R12") (pin "1") (pinfunction "1_1") (pintype "passive"))
    )
    (net (code "54") (name "Net-(IC8-+IN)") (class "Default")
      (node (ref "C11") (pin "1") (pinfunction "1_1") (pintype "passive"))
      (node (ref "IC8") (pin "3") (pinfunction "+IN_3") (pintype "input"))
      (node (ref "R11") (pin "2") (pinfunction "2_2") (pintype "passive"))
    )
    (net (code "55") (name "Net-(IC9-IN-)") (class "Default")
      (node (ref "C13") (pin "1") (pinfunction "1_1") (pintype "passive"))
      (node (ref "IC9") (pin "4") (pinfunction "IN-_4") (pintype "bidirectional"))
      (node (ref "J5") (pin "1") (pinfunction "1_1") (pintype "bidirectional"))
      (node (ref "R13") (pin "1") (pinfunction "1_1") (pintype "passive"))
    )
    (net (code "56") (name "Net-(IC9-OUT)") (class "Default")
      (node (ref "C13") (pin "2") (pinfunction "2_2") (pintype "passive"))
      (node (ref "IC9") (pin "1") (pinfunction "OUT_1") (pintype "bidirectional"))
      (node (ref "R13") (pin "2") (pinfunction "2_2") (pintype "passive"))
      (node (ref "R15") (pin "1") (pinfunction "1_1") (pintype "passive"))
    )
    (net (code "57") (name "Net-(IC10-+IN)") (class "Default")
      (node (ref "C14") (pin "1") (pinfunction "1_1") (pintype "passive"))
      (node (ref "IC10") (pin "3") (pinfunction "+IN_3") (pintype "input"))
      (node (ref "R14") (pin "2") (pinfunction "2_2") (pintype "passive"))
    )
    (net (code "58") (name "Net-(IC11-IN-)") (class "Default")
      (node (ref "C16") (pin "1") (pinfunction "1_1") (pintype "passive"))
      (node (ref "IC11") (pin "4") (pinfunction "IN-_4") (pintype "bidirectional"))
      (node (ref "J6") (pin "1") (pinfunction "1_1") (pintype "bidirectional"))
      (node (ref "R16") (pin "1") (pinfunction "1_1") (pintype "passive"))
    )
    (net (code "59") (name "Net-(IC11-OUT)") (class "Default")
      (node (ref "C16") (pin "2") (pinfunction "2_2") (pintype "passive"))
      (node (ref "IC11") (pin "1") (pinfunction "OUT_1") (pintype "bidirectional"))
      (node (ref "R16") (pin "2") (pinfunction "2_2") (pintype "passive"))
      (node (ref "R18") (pin "1") (pinfunction "1_1") (pintype "passive"))
    )
    (net (code "60") (name "Net-(IC12-+IN)") (class "Default")
      (node (ref "C17") (pin "1") (pinfunction "1_1") (pintype "passive"))
      (node (ref "IC12") (pin "3") (pinfunction "+IN_3") (pintype "input"))
      (node (ref "R17") (pin "2") (pinfunction "2_2") (pintype "passive"))
    )
    (net (code "61") (name "Net-(IC13-IN-)") (class "Default")
      (node (ref "C19") (pin "1") (pinfunction "1_1") (pintype "passive"))
      (node (ref "IC13") (pin "4") (pinfunction "IN-_4") (pintype "bidirectional"))
      (node (ref "J7") (pin "1") (pinfunction "1_1") (pintype "bidirectional"))
      (node (ref "R19") (pin "1") (pinfunction "1_1") (pintype "passive"))
    )
    (net (code "62") (name "Net-(IC13-OUT)") (class "Default")
      (node (ref "C19") (pin "2") (pinfunction "2_2") (pintype "passive"))
      (node (ref "IC13") (pin "1") (pinfunction "OUT_1") (pintype "bidirectional"))
      (node (ref "R19") (pin "2") (pinfunction "2_2") (pintype "passive"))
      (node (ref "R21") (pin "1") (pinfunction "1_1") (pintype "passive"))
    )
    (net (code "63") (name "Net-(IC14-+IN)") (class "Default")
      (node (ref "C20") (pin "1") (pinfunction "1_1") (pintype "passive"))
      (node (ref "IC14") (pin "3") (pinfunction "+IN_3") (pintype "input"))
      (node (ref "R20") (pin "2") (pinfunction "2_2") (pintype "passive"))
    )
    (net (code "64") (name "Net-(IC15-IN-)") (class "Default")
      (node (ref "C22") (pin "1") (pinfunction "1_1") (pintype "passive"))
      (node (ref "IC15") (pin "4") (pinfunction "IN-_4") (pintype "bidirectional"))
      (node (ref "J8") (pin "1") (pinfunction "1_1") (pintype "bidirectional"))
      (node (ref "R22") (pin "1") (pinfunction "1_1") (pintype "passive"))
    )
    (net (code "65") (name "Net-(IC15-OUT)") (class "Default")
      (node (ref "C22") (pin "2") (pinfunction "2_2") (pintype "passive"))
      (node (ref "IC15") (pin "1") (pinfunction "OUT_1") (pintype "bidirectional"))
      (node (ref "R22") (pin "2") (pinfunction "2_2") (pintype "passive"))
      (node (ref "R24") (pin "1") (pinfunction "1_1") (pintype "passive"))
    )
    (net (code "66") (name "Net-(IC16-+IN)") (class "Default")
      (node (ref "C23") (pin "1") (pinfunction "1_1") (pintype "passive"))
      (node (ref "IC16") (pin "3") (pinfunction "+IN_3") (pintype "input"))
      (node (ref "R23") (pin "2") (pinfunction "2_2") (pintype "passive"))
    )
    (net (code "67") (name "Net-(IC17-VIN+)") (class "Default")
      (node (ref "C25") (pin "1") (pinfunction "1_1") (pintype "passive"))
      (node (ref "IC17") (pin "8") (pinfunction "VIN+_8") (pintype "bidirectional"))
      (node (ref "R25") (pin "2") (pinfunction "2_2") (pintype "passive"))
      (node (ref "R26") (pin "1") (pinfunction "1_1") (pintype "passive"))
    )
    (net (code "68") (name "Net-(IC17-VIN-)") (class "Default")
      (node (ref "C26") (pin "1") (pinfunction "1_1") (pintype "passive"))
      (node (ref "IC17") (pin "1") (pinfunction "VIN-_1") (pintype "bidirectional"))
      (node (ref "R28") (pin "2") (pinfunction "2_2") (pintype "passive"))
      (node (ref "R30") (pin "1") (pinfunction "1_1") (pintype "passive"))
    )
    (net (code "69") (name "Net-(IC17-VOUT+)") (class "Default")
      (node (ref "C26") (pin "2") (pinfunction "2_2") (pintype "passive"))
      (node (ref "IC17") (pin "4") (pinfunction "VOUT+_4") (pintype "bidirectional"))
      (node (ref "R29") (pin "2") (pinfunction "2_2") (pintype "passive"))
    )
    (net (code "70") (name "Net-(IC17-VOUT-)") (class "Default")
      (node (ref "C25") (pin "2") (pinfunction "2_2") (pintype "passive"))
      (node (ref "IC17") (pin "5") (pinfunction "VOUT-_5") (pintype "bidirectional"))
      (node (ref "R27") (pin "1") (pinfunction "1_1") (pintype "passive"))
    )
    (net (code "71") (name "Net-(IC18-VIN+)") (class "Default")
      (node (ref "C28") (pin "1") (pinfunction "1_1") (pintype "passive"))
      (node (ref "IC18") (pin "8") (pinfunction "VIN+_8") (pintype "bidirectional"))
      (node (ref "R31") (pin "2") (pinfunction "2_2") (pintype "passive"))
      (node (ref "R32") (pin "1") (pinfunction "1_1") (pintype "passive"))
    )
    (net (code "72") (name "Net-(IC18-VIN-)") (class "Default")
      (node (ref "C29") (pin "1") (pinfunction "1_1") (pintype "passive"))
      (node (ref "IC18") (pin "1") (pinfunction "VIN-_1") (pintype "bidirectional"))
      (node (ref "R34") (pin "2") (pinfunction "2_2") (pintype "passive"))
      (node (ref "R36") (pin "1") (pinfunction "1_1") (pintype "passive"))
    )
    (net (code "73") (name "Net-(IC18-VOUT+)") (class "Default")
      (node (ref "C29") (pin "2") (pinfunction "2_2") (pintype "passive"))
      (node (ref "IC18") (pin "4") (pinfunction "VOUT+_4") (pintype "bidirectional"))
      (node (ref "R35") (pin "2") (pinfunction "2_2") (pintype "passive"))
    )
    (net (code "74") (name "Net-(IC18-VOUT-)") (class "Default")
      (node (ref "C28") (pin "2") (pinfunction "2_2") (pintype "passive"))
      (node (ref "IC18") (pin "5") (pinfunction "VOUT-_5") (pintype "bidirectional"))
      (node (ref "R33") (pin "1") (pinfunction "1_1") (pintype "passive"))
    )
    (net (code "75") (name "Net-(IC19-VIN+)") (class "Default")
      (node (ref "C31") (pin "1") (pinfunction "1_1") (pintype "passive"))
      (node (ref "IC19") (pin "8") (pinfunction "VIN+_8") (pintype "bidirectional"))
      (node (ref "R37") (pin "2") (pinfunction "2_2") (pintype "passive"))
      (node (ref "R38") (pin "1") (pinfunction "1_1") (pintype "passive"))
    )
    (net (code "76") (name "Net-(IC19-VIN-)") (class "Default")
      (node (ref "C32") (pin "1") (pinfunction "1_1") (pintype "passive"))
      (node (ref "IC19") (pin "1") (pinfunction "VIN-_1") (pintype "bidirectional"))
      (node (ref "R40") (pin "2") (pinfunction "2_2") (pintype "passive"))
      (node (ref "R42") (pin "1") (pinfunction "1_1") (pintype "passive"))
    )
    (net (code "77") (name "Net-(IC19-VOUT+)") (class "Default")
      (node (ref "C32") (pin "2") (pinfunction "2_2") (pintype "passive"))
      (node (ref "IC19") (pin "4") (pinfunction "VOUT+_4") (pintype "bidirectional"))
      (node (ref "R41") (pin "2") (pinfunction "2_2") (pintype "passive"))
    )
    (net (code "78") (name "Net-(IC19-VOUT-)") (class "Default")
      (node (ref "C31") (pin "2") (pinfunction "2_2") (pintype "passive"))
      (node (ref "IC19") (pin "5") (pinfunction "VOUT-_5") (pintype "bidirectional"))
      (node (ref "R39") (pin "1") (pinfunction "1_1") (pintype "passive"))
    )
    (net (code "79") (name "Net-(IC20-VIN+)") (class "Default")
      (node (ref "C34") (pin "1") (pinfunction "1_1") (pintype "passive"))
      (node (ref "IC20") (pin "8") (pinfunction "VIN+_8") (pintype "bidirectional"))
      (node (ref "R43") (pin "2") (pinfunction "2_2") (pintype "passive"))
      (node (ref "R44") (pin "1") (pinfunction "1_1") (pintype "passive"))
    )
    (net (code "80") (name "Net-(IC20-VIN-)") (class "Default")
      (node (ref "C35") (pin "1") (pinfunction "1_1") (pintype "passive"))
      (node (ref "IC20") (pin "1") (pinfunction "VIN-_1") (pintype "bidirectional"))
      (node (ref "R46") (pin "2") (pinfunction "2_2") (pintype "passive"))
      (node (ref "R48") (pin "1") (pinfunction "1_1") (pintype "passive"))
    )
    (net (code "81") (name "Net-(IC20-VOUT+)") (class "Default")
      (node (ref "C35") (pin "2") (pinfunction "2_2") (pintype "passive"))
      (node (ref "IC20") (pin "4") (pinfunction "VOUT+_4") (pintype "bidirectional"))
      (node (ref "R47") (pin "2") (pinfunction "2_2") (pintype "passive"))
    )
    (net (code "82") (name "Net-(IC20-VOUT-)") (class "Default")
      (node (ref "C34") (pin "2") (pinfunction "2_2") (pintype "passive"))
      (node (ref "IC20") (pin "5") (pinfunction "VOUT-_5") (pintype "bidirectional"))
      (node (ref "R45") (pin "1") (pinfunction "1_1") (pintype "passive"))
    )
    (net (code "83") (name "Net-(IC21-VIN+)") (class "Default")
      (node (ref "C37") (pin "1") (pinfunction "1_1") (pintype "passive"))
      (node (ref "IC21") (pin "8") (pinfunction "VIN+_8") (pintype "bidirectional"))
      (node (ref "R49") (pin "2") (pinfunction "2_2") (pintype "passive"))
      (node (ref "R50") (pin "1") (pinfunction "1_1") (pintype "passive"))
    )
    (net (code "84") (name "Net-(IC21-VIN-)") (class "Default")
      (node (ref "C38") (pin "1") (pinfunction "1_1") (pintype "passive"))
      (node (ref "IC21") (pin "1") (pinfunction "VIN-_1") (pintype "bidirectional"))
      (node (ref "R52") (pin "2") (pinfunction "2_2") (pintype "passive"))
      (node (ref "R54") (pin "1") (pinfunction "1_1") (pintype "passive"))
    )
    (net (code "85") (name "Net-(IC21-VOUT+)") (class "Default")
      (node (ref "C38") (pin "2") (pinfunction "2_2") (pintype "passive"))
      (node (ref "IC21") (pin "4") (pinfunction "VOUT+_4") (pintype "bidirectional"))
      (node (ref "R53") (pin "2") (pinfunction "2_2") (pintype "passive"))
    )
    (net (code "86") (name "Net-(IC21-VOUT-)") (class "Default")
      (node (ref "C37") (pin "2") (pinfunction "2_2") (pintype "passive"))
      (node (ref "IC21") (pin "5") (pinfunction "VOUT-_5") (pintype "bidirectional"))
      (node (ref "R51") (pin "1") (pinfunction "1_1") (pintype "passive"))
    )
    (net (code "87") (name "Net-(IC22-VIN+)") (class "Default")
      (node (ref "C40") (pin "1") (pinfunction "1_1") (pintype "passive"))
      (node (ref "IC22") (pin "8") (pinfunction "VIN+_8") (pintype "bidirectional"))
      (node (ref "R55") (pin "2") (pinfunction "2_2") (pintype "passive"))
      (node (ref "R56") (pin "1") (pinfunction "1_1") (pintype "passive"))
    )
    (net (code "88") (name "Net-(IC22-VIN-)") (class "Default")
      (node (ref "C41") (pin "1") (pinfunction "1_1") (pintype "passive"))
      (node (ref "IC22") (pin "1") (pinfunction "VIN-_1") (pintype "bidirectional"))
      (node (ref "R58") (pin "2") (pinfunction "2_2") (pintype "passive"))
      (node (ref "R60") (pin "1") (pinfunction "1_1") (pintype "passive"))
    )
    (net (code "89") (name "Net-(IC22-VOUT+)") (class "Default")
      (node (ref "C41") (pin "2") (pinfunction "2_2") (pintype "passive"))
      (node (ref "IC22") (pin "4") (pinfunction "VOUT+_4") (pintype "bidirectional"))
      (node (ref "R59") (pin "2") (pinfunction "2_2") (pintype "passive"))
    )
    (net (code "90") (name "Net-(IC22-VOUT-)") (class "Default")
      (node (ref "C40") (pin "2") (pinfunction "2_2") (pintype "passive"))
      (node (ref "IC22") (pin "5") (pinfunction "VOUT-_5") (pintype "bidirectional"))
      (node (ref "R57") (pin "1") (pinfunction "1_1") (pintype "passive"))
    )
    (net (code "91") (name "Net-(IC23-VIN+)") (class "Default")
      (node (ref "C43") (pin "1") (pinfunction "1_1") (pintype "passive"))
      (node (ref "IC23") (pin "8") (pinfunction "VIN+_8") (pintype "bidirectional"))
      (node (ref "R61") (pin "2") (pinfunction "2_2") (pintype "passive"))
      (node (ref "R62") (pin "1") (pinfunction "1_1") (pintype "passive"))
    )
    (net (code "92") (name "Net-(IC23-VIN-)") (class "Default")
      (node (ref "C44") (pin "1") (pinfunction "1_1") (pintype "passive"))
      (node (ref "IC23") (pin "1") (pinfunction "VIN-_1") (pintype "bidirectional"))
      (node (ref "R64") (pin "2") (pinfunction "2_2") (pintype "passive"))
      (node (ref "R66") (pin "1") (pinfunction "1_1") (pintype "passive"))
    )
    (net (code "93") (name "Net-(IC23-VOUT+)") (class "Default")
      (node (ref "C44") (pin "2") (pinfunction "2_2") (pintype "passive"))
      (node (ref "IC23") (pin "4") (pinfunction "VOUT+_4") (pintype "bidirectional"))
      (node (ref "R65") (pin "2") (pinfunction "2_2") (pintype "passive"))
    )
    (net (code "94") (name "Net-(IC23-VOUT-)") (class "Default")
      (node (ref "C43") (pin "2") (pinfunction "2_2") (pintype "passive"))
      (node (ref "IC23") (pin "5") (pinfunction "VOUT-_5") (pintype "bidirectional"))
      (node (ref "R63") (pin "1") (pinfunction "1_1") (pintype "passive"))
    )
    (net (code "95") (name "Net-(IC24-VIN+)") (class "Default")
      (node (ref "C46") (pin "1") (pinfunction "1_1") (pintype "passive"))
      (node (ref "IC24") (pin "8") (pinfunction "VIN+_8") (pintype "bidirectional"))
      (node (ref "R67") (pin "2") (pinfunction "2_2") (pintype "passive"))
      (node (ref "R68") (pin "1") (pinfunction "1_1") (pintype "passive"))
    )
    (net (code "96") (name "Net-(IC24-VIN-)") (class "Default")
      (node (ref "C47") (pin "1") (pinfunction "1_1") (pintype "passive"))
      (node (ref "IC24") (pin "1") (pinfunction "VIN-_1") (pintype "bidirectional"))
      (node (ref "R70") (pin "2") (pinfunction "2_2") (pintype "passive"))
      (node (ref "R72") (pin "1") (pinfunction "1_1") (pintype "passive"))
    )
    (net (code "97") (name "Net-(IC24-VOUT+)") (class "Default")
      (node (ref "C47") (pin "2") (pinfunction "2_2") (pintype "passive"))
      (node (ref "IC24") (pin "4") (pinfunction "VOUT+_4") (pintype "bidirectional"))
      (node (ref "R71") (pin "2") (pinfunction "2_2") (pintype "passive"))
    )
    (net (code "98") (name "Net-(IC24-VOUT-)") (class "Default")
      (node (ref "C46") (pin "2") (pinfunction "2_2") (pintype "passive"))
      (node (ref "IC24") (pin "5") (pinfunction "VOUT-_5") (pintype "bidirectional"))
      (node (ref "R69") (pin "1") (pinfunction "1_1") (pintype "passive"))
    )
    (net (code "99") (name "Net-(IC25-C)") (class "Default")
      (node (ref "IC25") (pin "6") (pinfunction "C_6") (pintype "passive"))
      (node (ref "R74") (pin "1") (pinfunction "1_1") (pintype "passive"))
    )
    (net (code "100") (name "Net-(IC25-C1)") (class "Default")
      (node (ref "IC25") (pin "8") (pinfunction "C1_8") (pintype "passive"))
      (node (ref "R73") (pin "1") (pinfunction "1_1") (pintype "passive"))
    )
    (net (code "101") (name "Net-(U1-IN-)") (class "Default")
      (node (ref "R78") (pin "1") (pinfunction "1_1") (pintype "passive"))
      (node (ref "U1") (pin "2") (pinfunction "IN-_2") (pintype "input"))
      (node (ref "U1") (pin "6") (pinfunction "OUTPUT_6") (pintype "output"))
    )
    (net (code "102") (name "Net-(U2-IN+)") (class "Default")
      (node (ref "R75") (pin "2") (pinfunction "2_2") (pintype "passive"))
      (node (ref "U2") (pin "3") (pinfunction "IN+_3") (pintype "input"))
    )
    (net (code "103") (name "Net-(U2-IN-)") (class "Default")
      (node (ref "C51") (pin "1") (pinfunction "1_1") (pintype "passive"))
      (node (ref "R76") (pin "1") (pinfunction "1_1") (pintype "passive"))
      (node (ref "U2") (pin "2") (pinfunction "IN-_2") (pintype "input"))
    )
    (net (code "104") (name "Net-(U2-OUTPUT)") (class "Default")
      (node (ref "C51") (pin "2") (pinfunction "2_2") (pintype "passive"))
      (node (ref "R77") (pin "1") (pinfunction "1_1") (pintype "passive"))
      (node (ref "U2") (pin "6") (pinfunction "OUTPUT_6") (pintype "output"))
    )
    (net (code "105") (name "Net-(U3-~{PWDN1})") (class "Default")
      (node (ref "SJ1") (pin "2") (pinfunction "2_2") (pintype "passive"))
      (node (ref "U3") (pin "35") (pinfunction "~{PWDN8}_35") (pintype "input"))
      (node (ref "U3") (pin "36") (pinfunction "~{PWDN7}_36") (pintype "input"))
      (node (ref "U3") (pin "37") (pinfunction "~{PWDN6}_37") (pintype "input"))
      (node (ref "U3") (pin "38") (pinfunction "~{PWDN5}_38") (pintype "input"))
      (node (ref "U3") (pin "39") (pinfunction "~{PWDN4}_39") (pintype "input"))
      (node (ref "U3") (pin "40") (pinfunction "~{PWDN3}_40") (pintype "input"))
      (node (ref "U3") (pin "41") (pinfunction "~{PWDN2}_41") (pintype "input"))
      (node (ref "U3") (pin "42") (pinfunction "~{PWDN1}_42") (pintype "input"))
    )
    (net (code "106") (name "S1") (class "Default")
      (node (ref "C3") (pin "2") (pinfunction "2_2") (pintype "passive"))
      (node (ref "IC3") (pin "1") (pinfunction "OUT_1") (pintype "output"))
      (node (ref "IC3") (pin "4") (pinfunction "-IN_4") (pintype "input"))
      (node (ref "R25") (pin "1") (pinfunction "1_1") (pintype "passive"))
    )
    (net (code "107") (name "S2") (class "Default")
      (node (ref "C6") (pin "2") (pinfunction "2_2") (pintype "passive"))
      (node (ref "IC4") (pin "1") (pinfunction "OUT_1") (pintype "output"))
      (node (ref "IC4") (pin "4") (pinfunction "-IN_4") (pintype "input"))
      (node (ref "R31") (pin "1") (pinfunction "1_1") (pintype "passive"))
    )
    (net (code "108") (name "S3") (class "Default")
      (node (ref "C9") (pin "2") (pinfunction "2_2") (pintype "passive"))
      (node (ref "IC6") (pin "1") (pinfunction "OUT_1") (pintype "output"))
      (node (ref "IC6") (pin "4") (pinfunction "-IN_4") (pintype "input"))
      (node (ref "R37") (pin "1") (pinfunction "1_1") (pintype "passive"))
    )
    (net (code "109") (name "S4") (class "Default")
      (node (ref "C12") (pin "2") (pinfunction "2_2") (pintype "passive"))
      (node (ref "IC8") (pin "1") (pinfunction "OUT_1") (pintype "output"))
      (node (ref "IC8") (pin "4") (pinfunction "-IN_4") (pintype "input"))
      (node (ref "R43") (pin "1") (pinfunction "1_1") (pintype "passive"))
    )
    (net (code "110") (name "S5") (class "Default")
      (node (ref "C15") (pin "2") (pinfunction "2_2") (pintype "passive"))
      (node (ref "IC10") (pin "1") (pinfunction "OUT_1") (pintype "output"))
      (node (ref "IC10") (pin "4") (pinfunction "-IN_4") (pintype "input"))
      (node (ref "R49") (pin "1") (pinfunction "1_1") (pintype "passive"))
    )
    (net (code "111") (name "S6") (class "Default")
      (node (ref "C18") (pin "2") (pinfunction "2_2") (pintype "passive"))
      (node (ref "IC12") (pin "1") (pinfunction "OUT_1") (pintype "output"))
      (node (ref "IC12") (pin "4") (pinfunction "-IN_4") (pintype "input"))
      (node (ref "R55") (pin "1") (pinfunction "1_1") (pintype "passive"))
    )
    (net (code "112") (name "S7") (class "Default")
      (node (ref "C21") (pin "2") (pinfunction "2_2") (pintype "passive"))
      (node (ref "IC14") (pin "1") (pinfunction "OUT_1") (pintype "output"))
      (node (ref "IC14") (pin "4") (pinfunction "-IN_4") (pintype "input"))
      (node (ref "R61") (pin "1") (pinfunction "1_1") (pintype "passive"))
    )
    (net (code "113") (name "S8") (class "Default")
      (node (ref "C24") (pin "2") (pinfunction "2_2") (pintype "passive"))
      (node (ref "IC16") (pin "1") (pinfunction "OUT_1") (pintype "output"))
      (node (ref "IC16") (pin "4") (pinfunction "-IN_4") (pintype "input"))
      (node (ref "R67") (pin "1") (pinfunction "1_1") (pintype "passive"))
    )
    (net (code "114") (name "SCLK") (class "Default")
      (node (ref "JP2") (pin "12") (pinfunction "12_12") (pintype "passive"))
      (node (ref "U3") (pin "28") (pinfunction "SCLK_28") (pintype "input"))
    )
    (net (code "115") (name "SYNC") (class "Default")
      (node (ref "JP2") (pin "2") (pinfunction "2_2") (pintype "passive"))
      (node (ref "U3") (pin "11") (pinfunction "~{SYNC}_11") (pintype "input"))
    )
    (net (code "116") (name "VCOM") (class "Default")
      (node (ref "C27") (pin "1") (pinfunction "1_1") (pintype "passive"))
      (node (ref "C30") (pin "1") (pinfunction "1_1") (pintype "passive"))
      (node (ref "C33") (pin "1") (pinfunction "1_1") (pintype "passive"))
      (node (ref "C36") (pin "1") (pinfunction "1_1") (pintype "passive"))
      (node (ref "C39") (pin "1") (pinfunction "1_1") (pintype "passive"))
      (node (ref "C42") (pin "1") (pinfunction "1_1") (pintype "passive"))
      (node (ref "C45") (pin "1") (pinfunction "1_1") (pintype "passive"))
      (node (ref "C48") (pin "1") (pinfunction "1_1") (pintype "passive"))
      (node (ref "IC17") (pin "2") (pinfunction "VOCM_2") (pintype "bidirectional"))
      (node (ref "IC18") (pin "2") (pinfunction "VOCM_2") (pintype "bidirectional"))
      (node (ref "IC19") (pin "2") (pinfunction "VOCM_2") (pintype "bidirectional"))
      (node (ref "IC20") (pin "2") (pinfunction "VOCM_2") (pintype "bidirectional"))
      (node (ref "IC21") (pin "2") (pinfunction "VOCM_2") (pintype "bidirectional"))
      (node (ref "IC22") (pin "2") (pinfunction "VOCM_2") (pintype "bidirectional"))
      (node (ref "IC23") (pin "2") (pinfunction "VOCM_2") (pintype "bidirectional"))
      (node (ref "IC24") (pin "2") (pinfunction "VOCM_2") (pintype "bidirectional"))
      (node (ref "R78") (pin "2") (pinfunction "2_2") (pintype "passive"))
    )
    (net (code "117") (name "VCOMM") (class "Default")
      (node (ref "C54") (pin "1") (pinfunction "1_1") (pintype "passive"))
      (node (ref "U1") (pin "3") (pinfunction "IN+_3") (pintype "input"))
      (node (ref "U3") (pin "55") (pinfunction "VCOM_55") (pintype "power_in"))
    )
    (net (code "118") (name "VREFP") (class "Default")
      (node (ref "C52") (pin "1") (pinfunction "1_1") (pintype "passive"))
      (node (ref "C53") (pin "1") (pinfunction "1_1") (pintype "passive"))
      (node (ref "R76") (pin "2") (pinfunction "2_2") (pintype "passive"))
      (node (ref "R77") (pin "2") (pinfunction "2_2") (pintype "passive"))
      (node (ref "U3") (pin "56") (pinfunction "VREFP_56") (pintype "power_in"))
    )
    (net (code "119") (name "unconnected-(IC17-ENABLE-Pad7)") (class "Default")
      (node (ref "IC17") (pin "7") (pinfunction "ENABLE_7") (pintype "bidirectional"))
    )
    (net (code "120") (name "unconnected-(IC18-ENABLE-Pad7)") (class "Default")
      (node (ref "IC18") (pin "7") (pinfunction "ENABLE_7") (pintype "bidirectional"))
    )
    (net (code "121") (name "unconnected-(IC19-ENABLE-Pad7)") (class "Default")
      (node (ref "IC19") (pin "7") (pinfunction "ENABLE_7") (pintype "bidirectional"))
    )
    (net (code "122") (name "unconnected-(IC20-ENABLE-Pad7)") (class "Default")
      (node (ref "IC20") (pin "7") (pinfunction "ENABLE_7") (pintype "bidirectional"))
    )
    (net (code "123") (name "unconnected-(IC21-ENABLE-Pad7)") (class "Default")
      (node (ref "IC21") (pin "7") (pinfunction "ENABLE_7") (pintype "bidirectional"))
    )
    (net (code "124") (name "unconnected-(IC22-ENABLE-Pad7)") (class "Default")
      (node (ref "IC22") (pin "7") (pinfunction "ENABLE_7") (pintype "bidirectional"))
    )
    (net (code "125") (name "unconnected-(IC23-ENABLE-Pad7)") (class "Default")
      (node (ref "IC23") (pin "7") (pinfunction "ENABLE_7") (pintype "bidirectional"))
    )
    (net (code "126") (name "unconnected-(IC24-ENABLE-Pad7)") (class "Default")
      (node (ref "IC24") (pin "7") (pinfunction "ENABLE_7") (pintype "bidirectional"))
    )
    (net (code "127") (name "unconnected-(IC25-NC-Pad1)") (class "Default")
      (node (ref "IC25") (pin "1") (pinfunction "NC_1") (pintype "no_connect"))
    )
    (net (code "128") (name "unconnected-(IC25-NC-Pad2)") (class "Default")
      (node (ref "IC25") (pin "2") (pinfunction "NC_2") (pintype "no_connect"))
    )
    (net (code "129") (name "unconnected-(IC25-NC-Pad3)") (class "Default")
      (node (ref "IC25") (pin "3") (pinfunction "NC_3") (pintype "no_connect"))
    )
    (net (code "130") (name "unconnected-(IC25-NC-Pad5)") (class "Default")
      (node (ref "IC25") (pin "5") (pinfunction "NC_5") (pintype "no_connect"))
    )
    (net (code "131") (name "unconnected-(IC25-NC-Pad7)") (class "Default")
      (node (ref "IC25") (pin "7") (pinfunction "NC_7") (pintype "no_connect"))
    )
    (net (code "132") (name "unconnected-(U1-NC-Pad8)") (class "Default")
      (node (ref "U1") (pin "8") (pinfunction "NC_8") (pintype "passive"))
    )
    (net (code "133") (name "unconnected-(U1-NC_2-Pad1)") (class "Default")
      (node (ref "U1") (pin "1") (pinfunction "NC_2_1") (pintype "passive"))
    )
    (net (code "134") (name "unconnected-(U1-NC_3-Pad5)") (class "Default")
      (node (ref "U1") (pin "5") (pinfunction "NC_3_5") (pintype "passive"))
    )
    (net (code "135") (name "unconnected-(U2-NC-Pad8)") (class "Default")
      (node (ref "U2") (pin "8") (pinfunction "NC_8") (pintype "passive"))
    )
    (net (code "136") (name "unconnected-(U2-NC_2-Pad1)") (class "Default")
      (node (ref "U2") (pin "1") (pinfunction "NC_2_1") (pintype "passive"))
    )
    (net (code "137") (name "unconnected-(U2-NC_3-Pad5)") (class "Default")
      (node (ref "U2") (pin "5") (pinfunction "NC_3_5") (pintype "passive"))
    )
    (net (code "138") (name "unconnected-(U3-NC-Pad33)") (class "Default")
      (node (ref "U3") (pin "33") (pinfunction "NC_33") (pintype "no_connect"))
    )
  )
)
